# motoko_ice_dragon_x.net
KiCad netlist of a schematic drawn in EasyEDA Pro
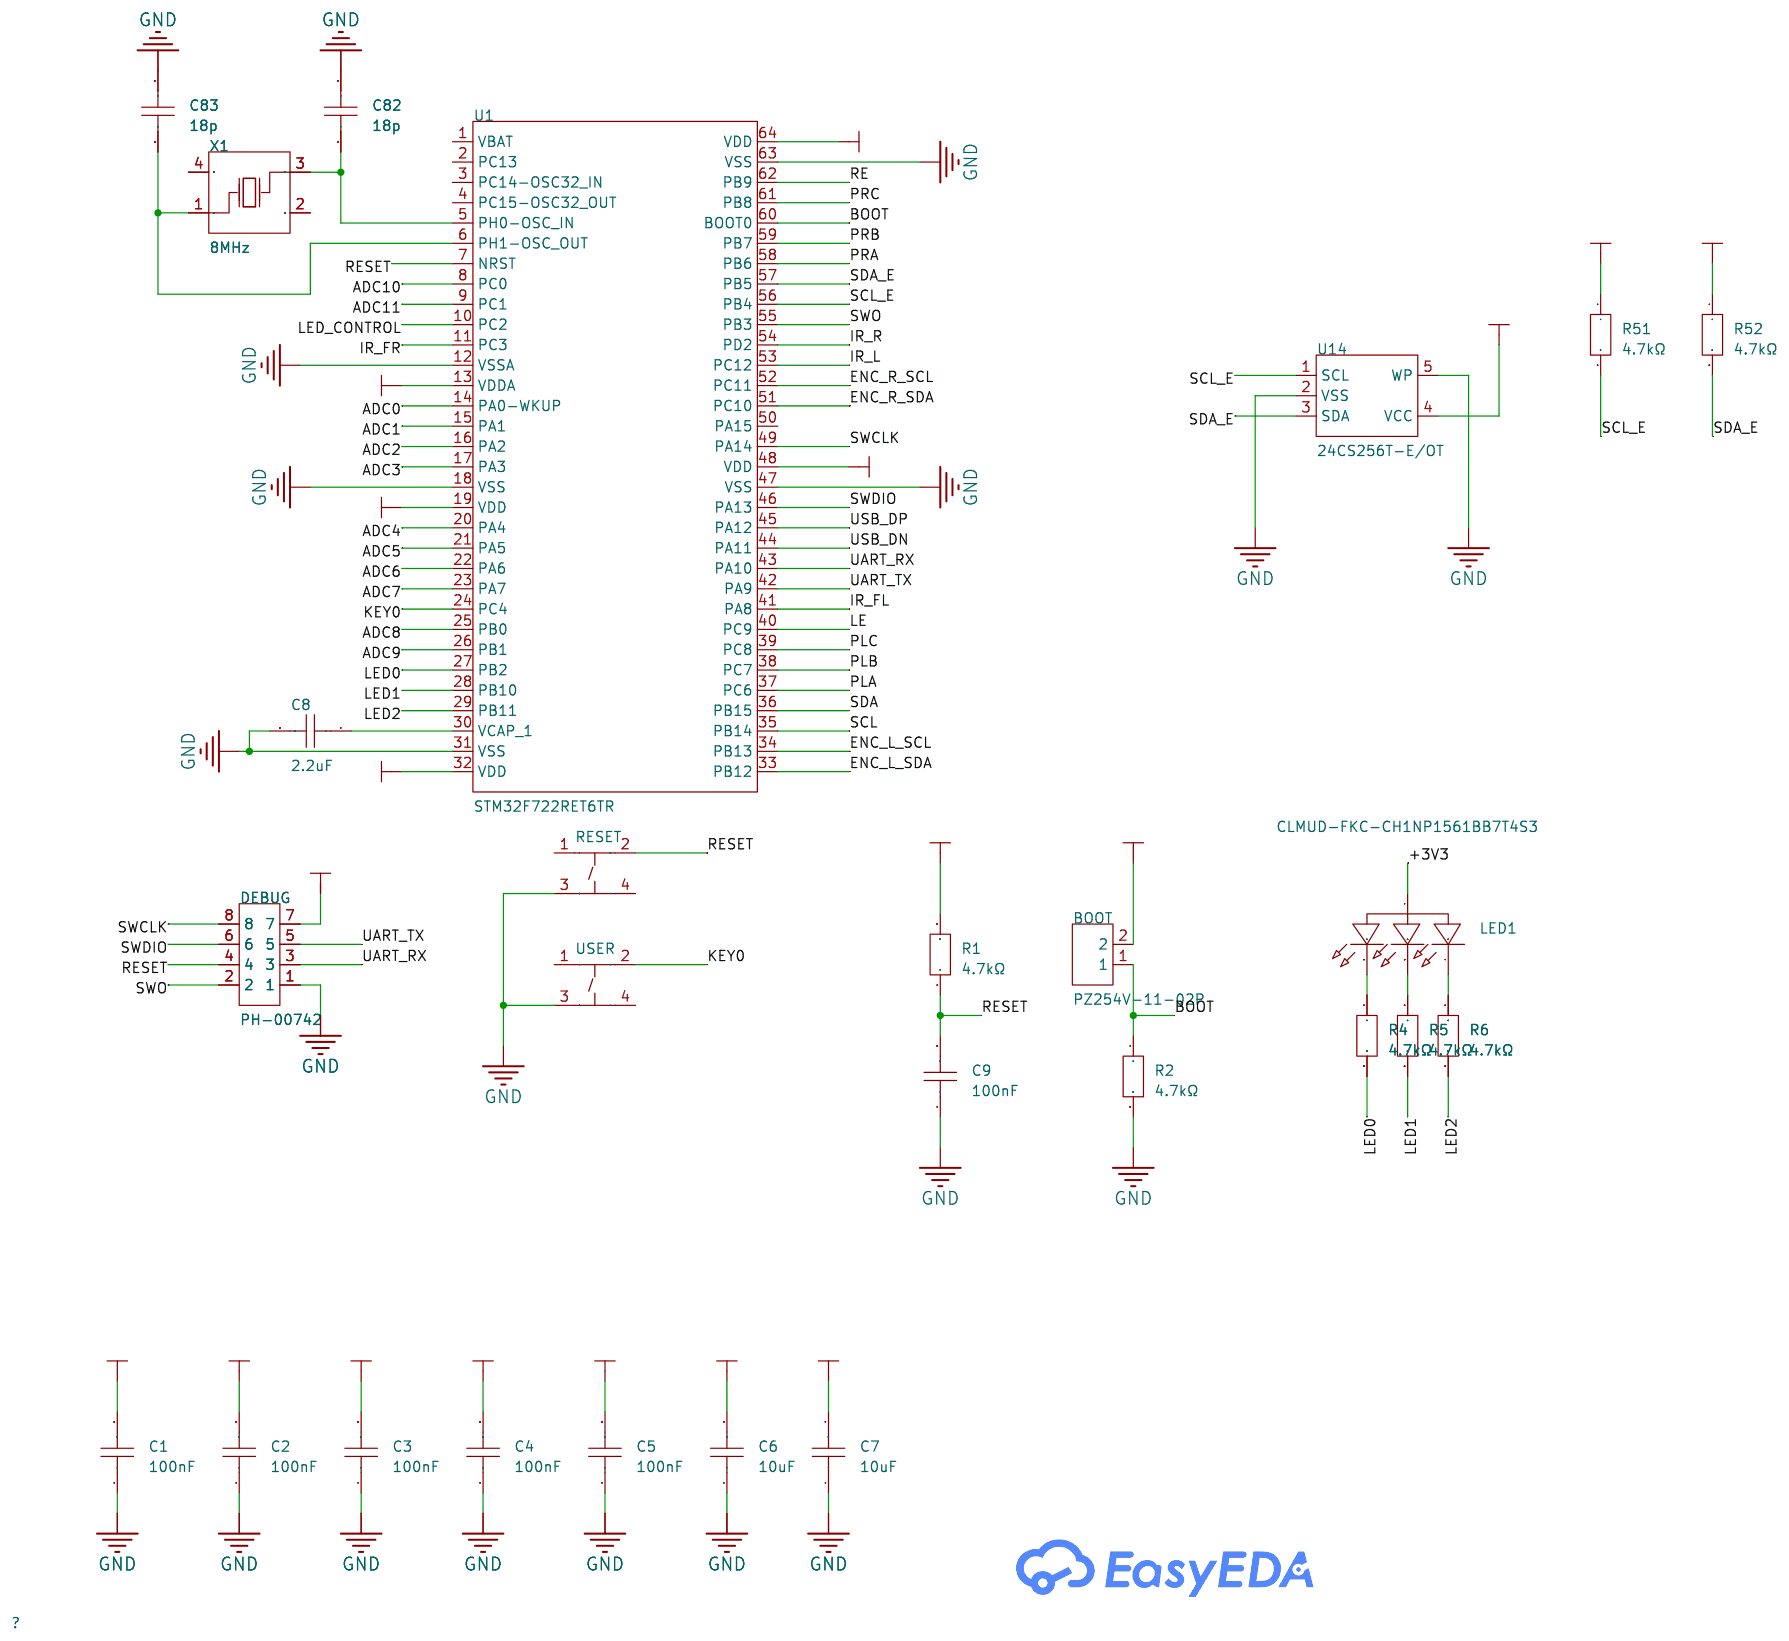
[diagram p0: main]
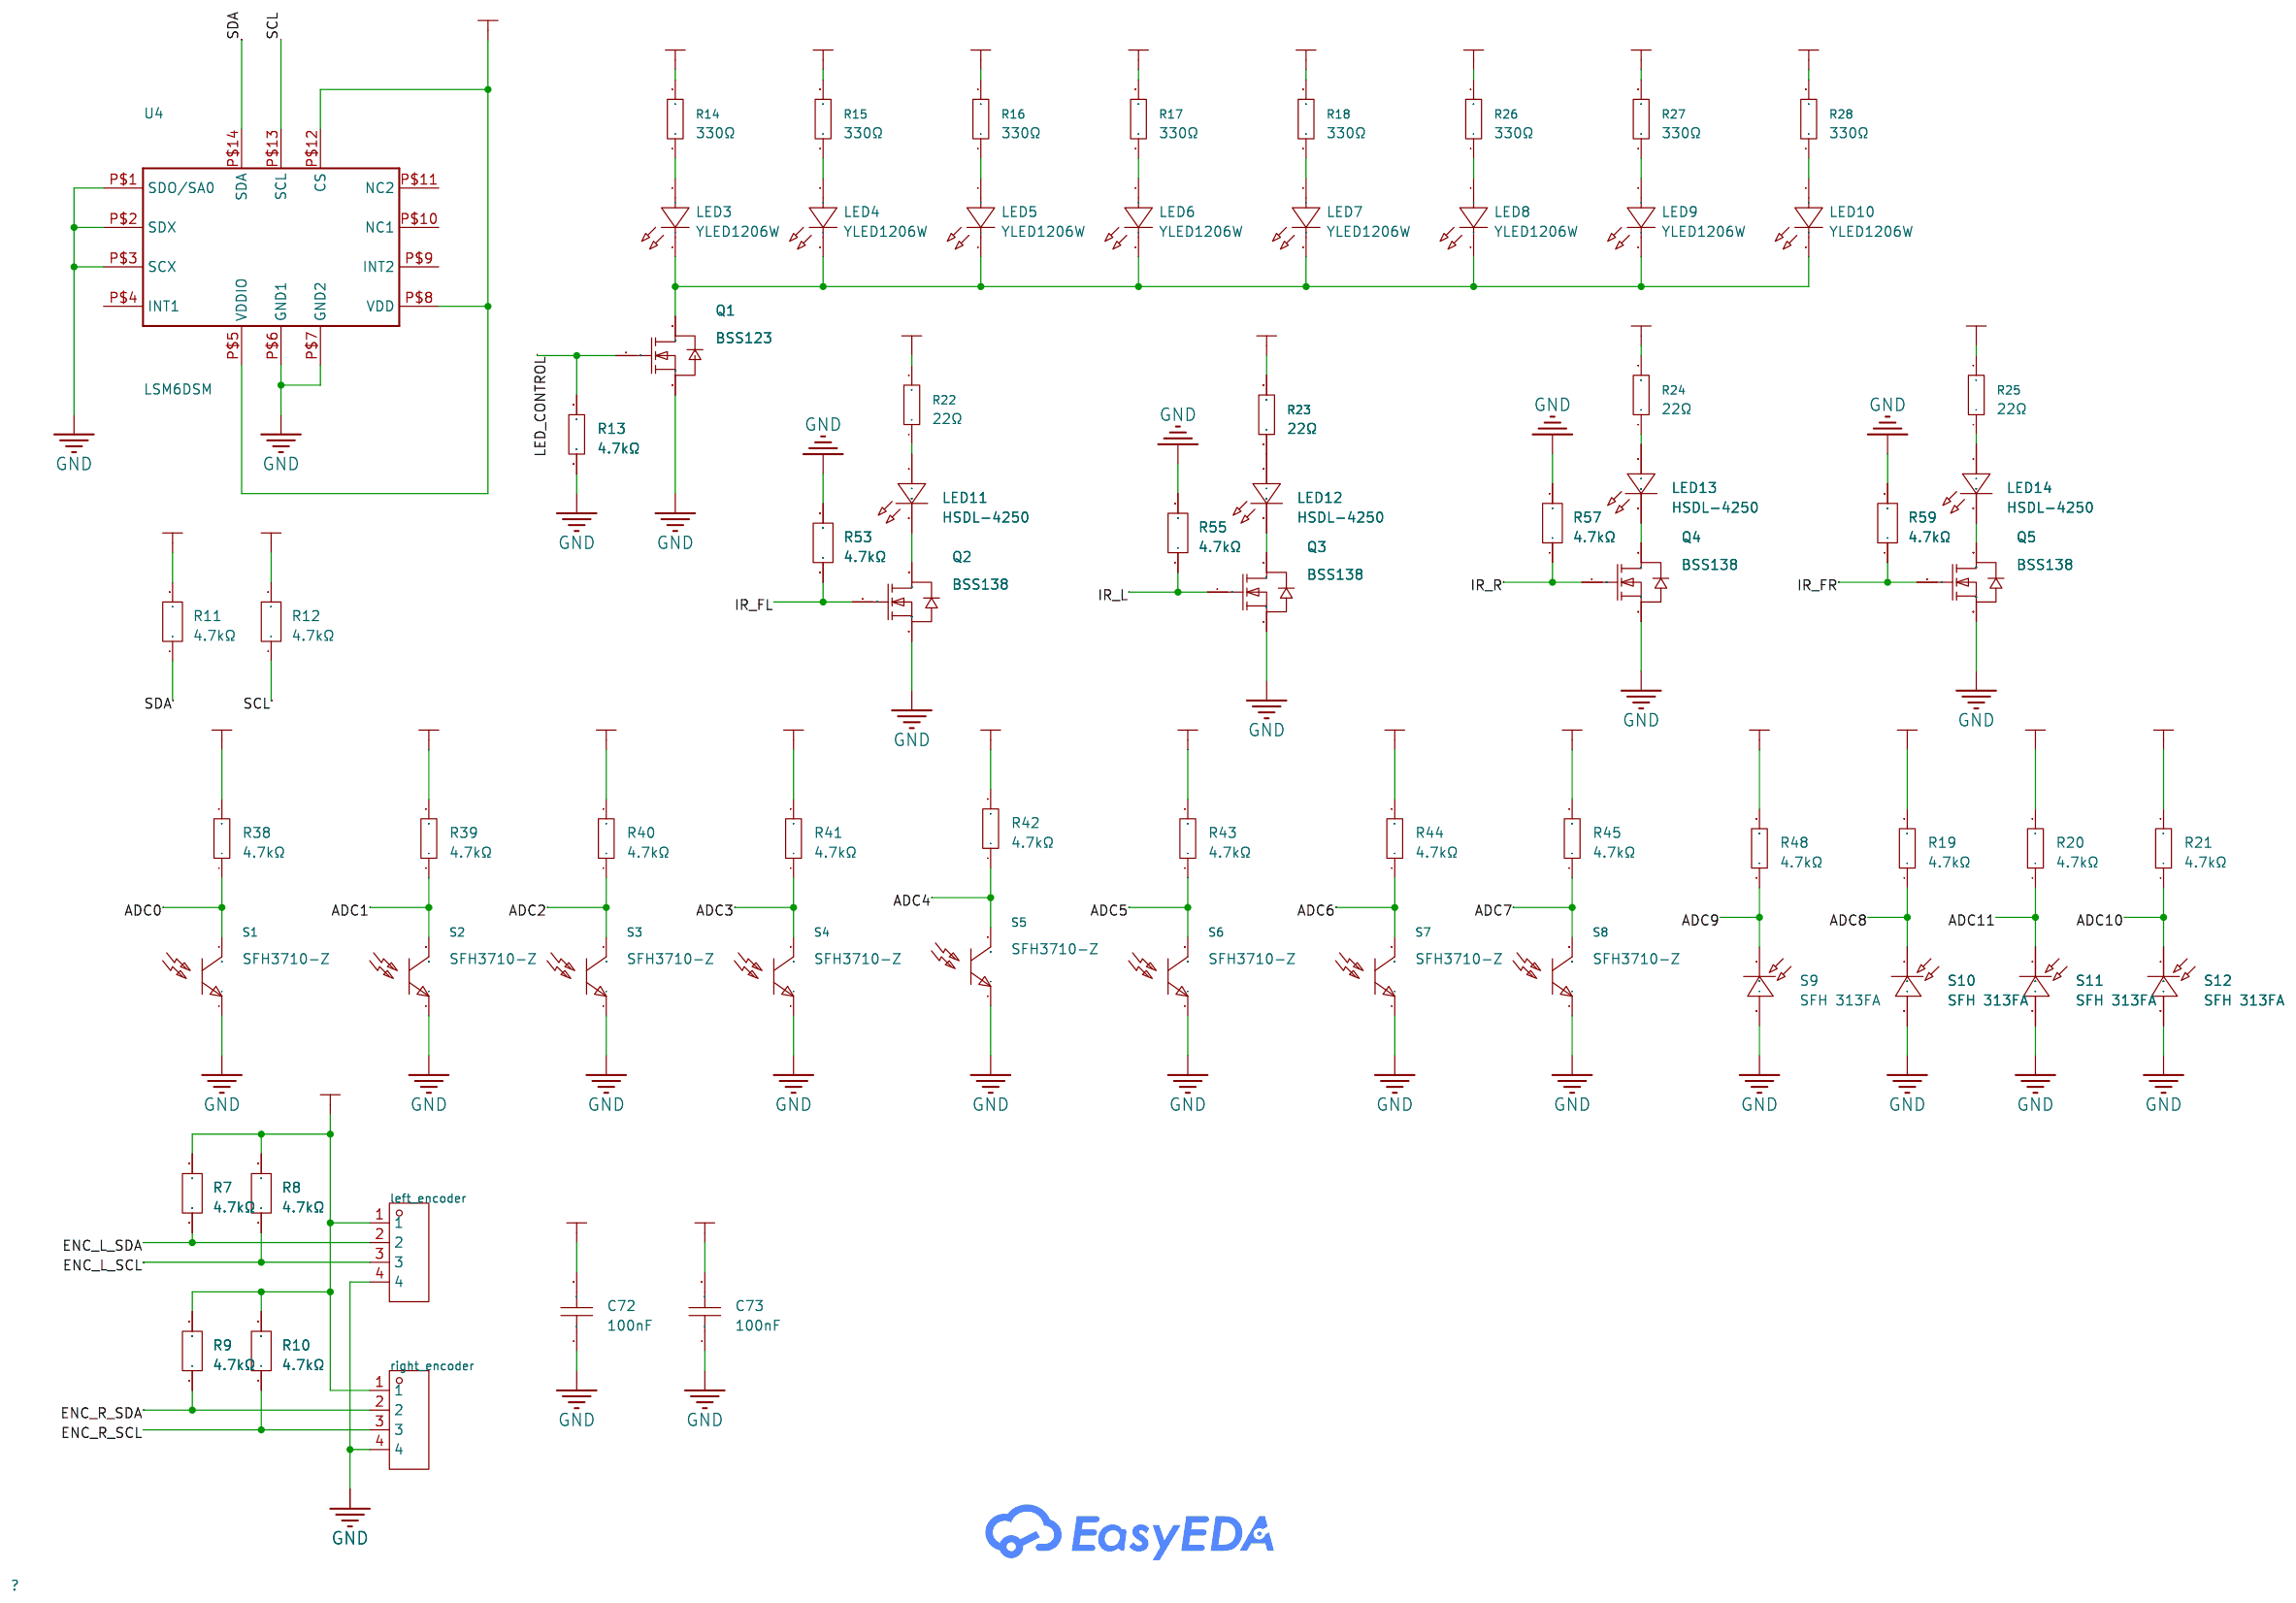
[diagram p1: sensors]
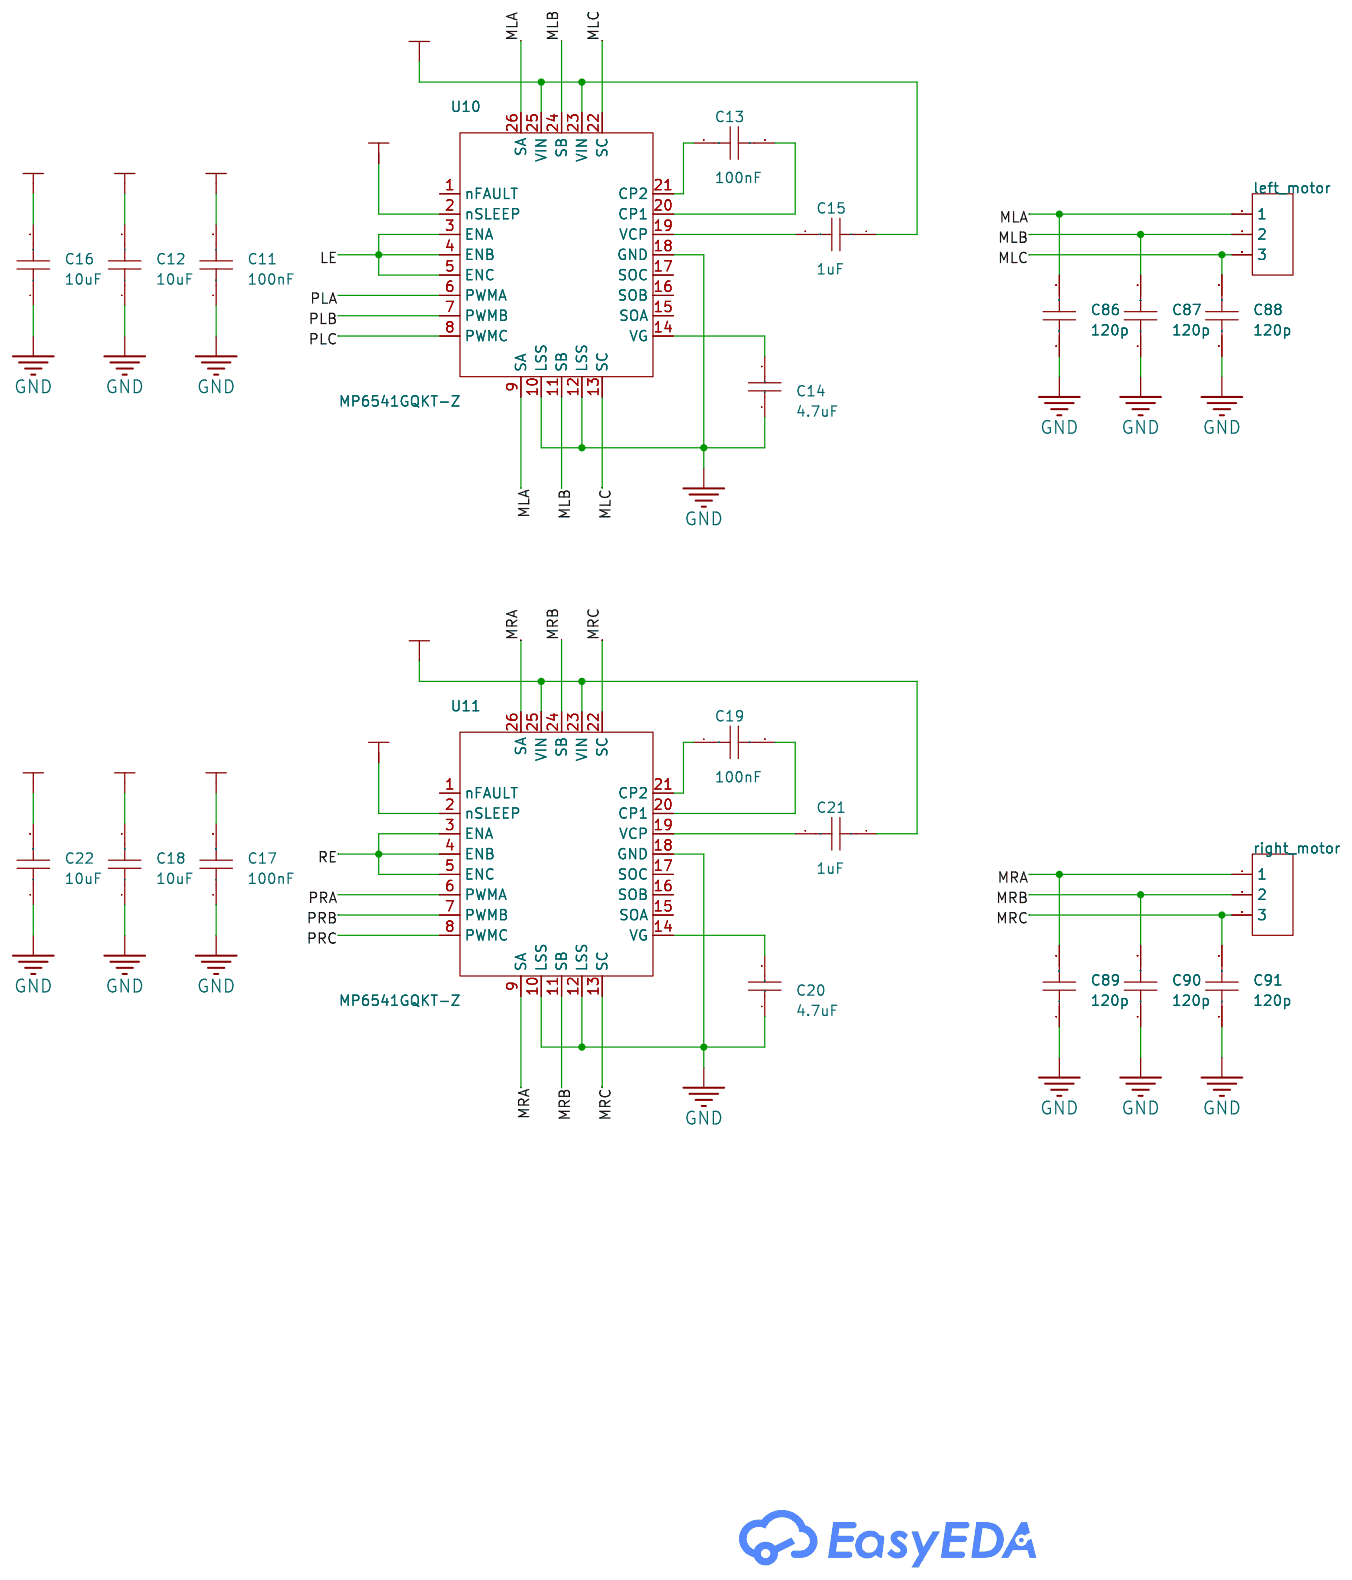
[diagram p2: motors]
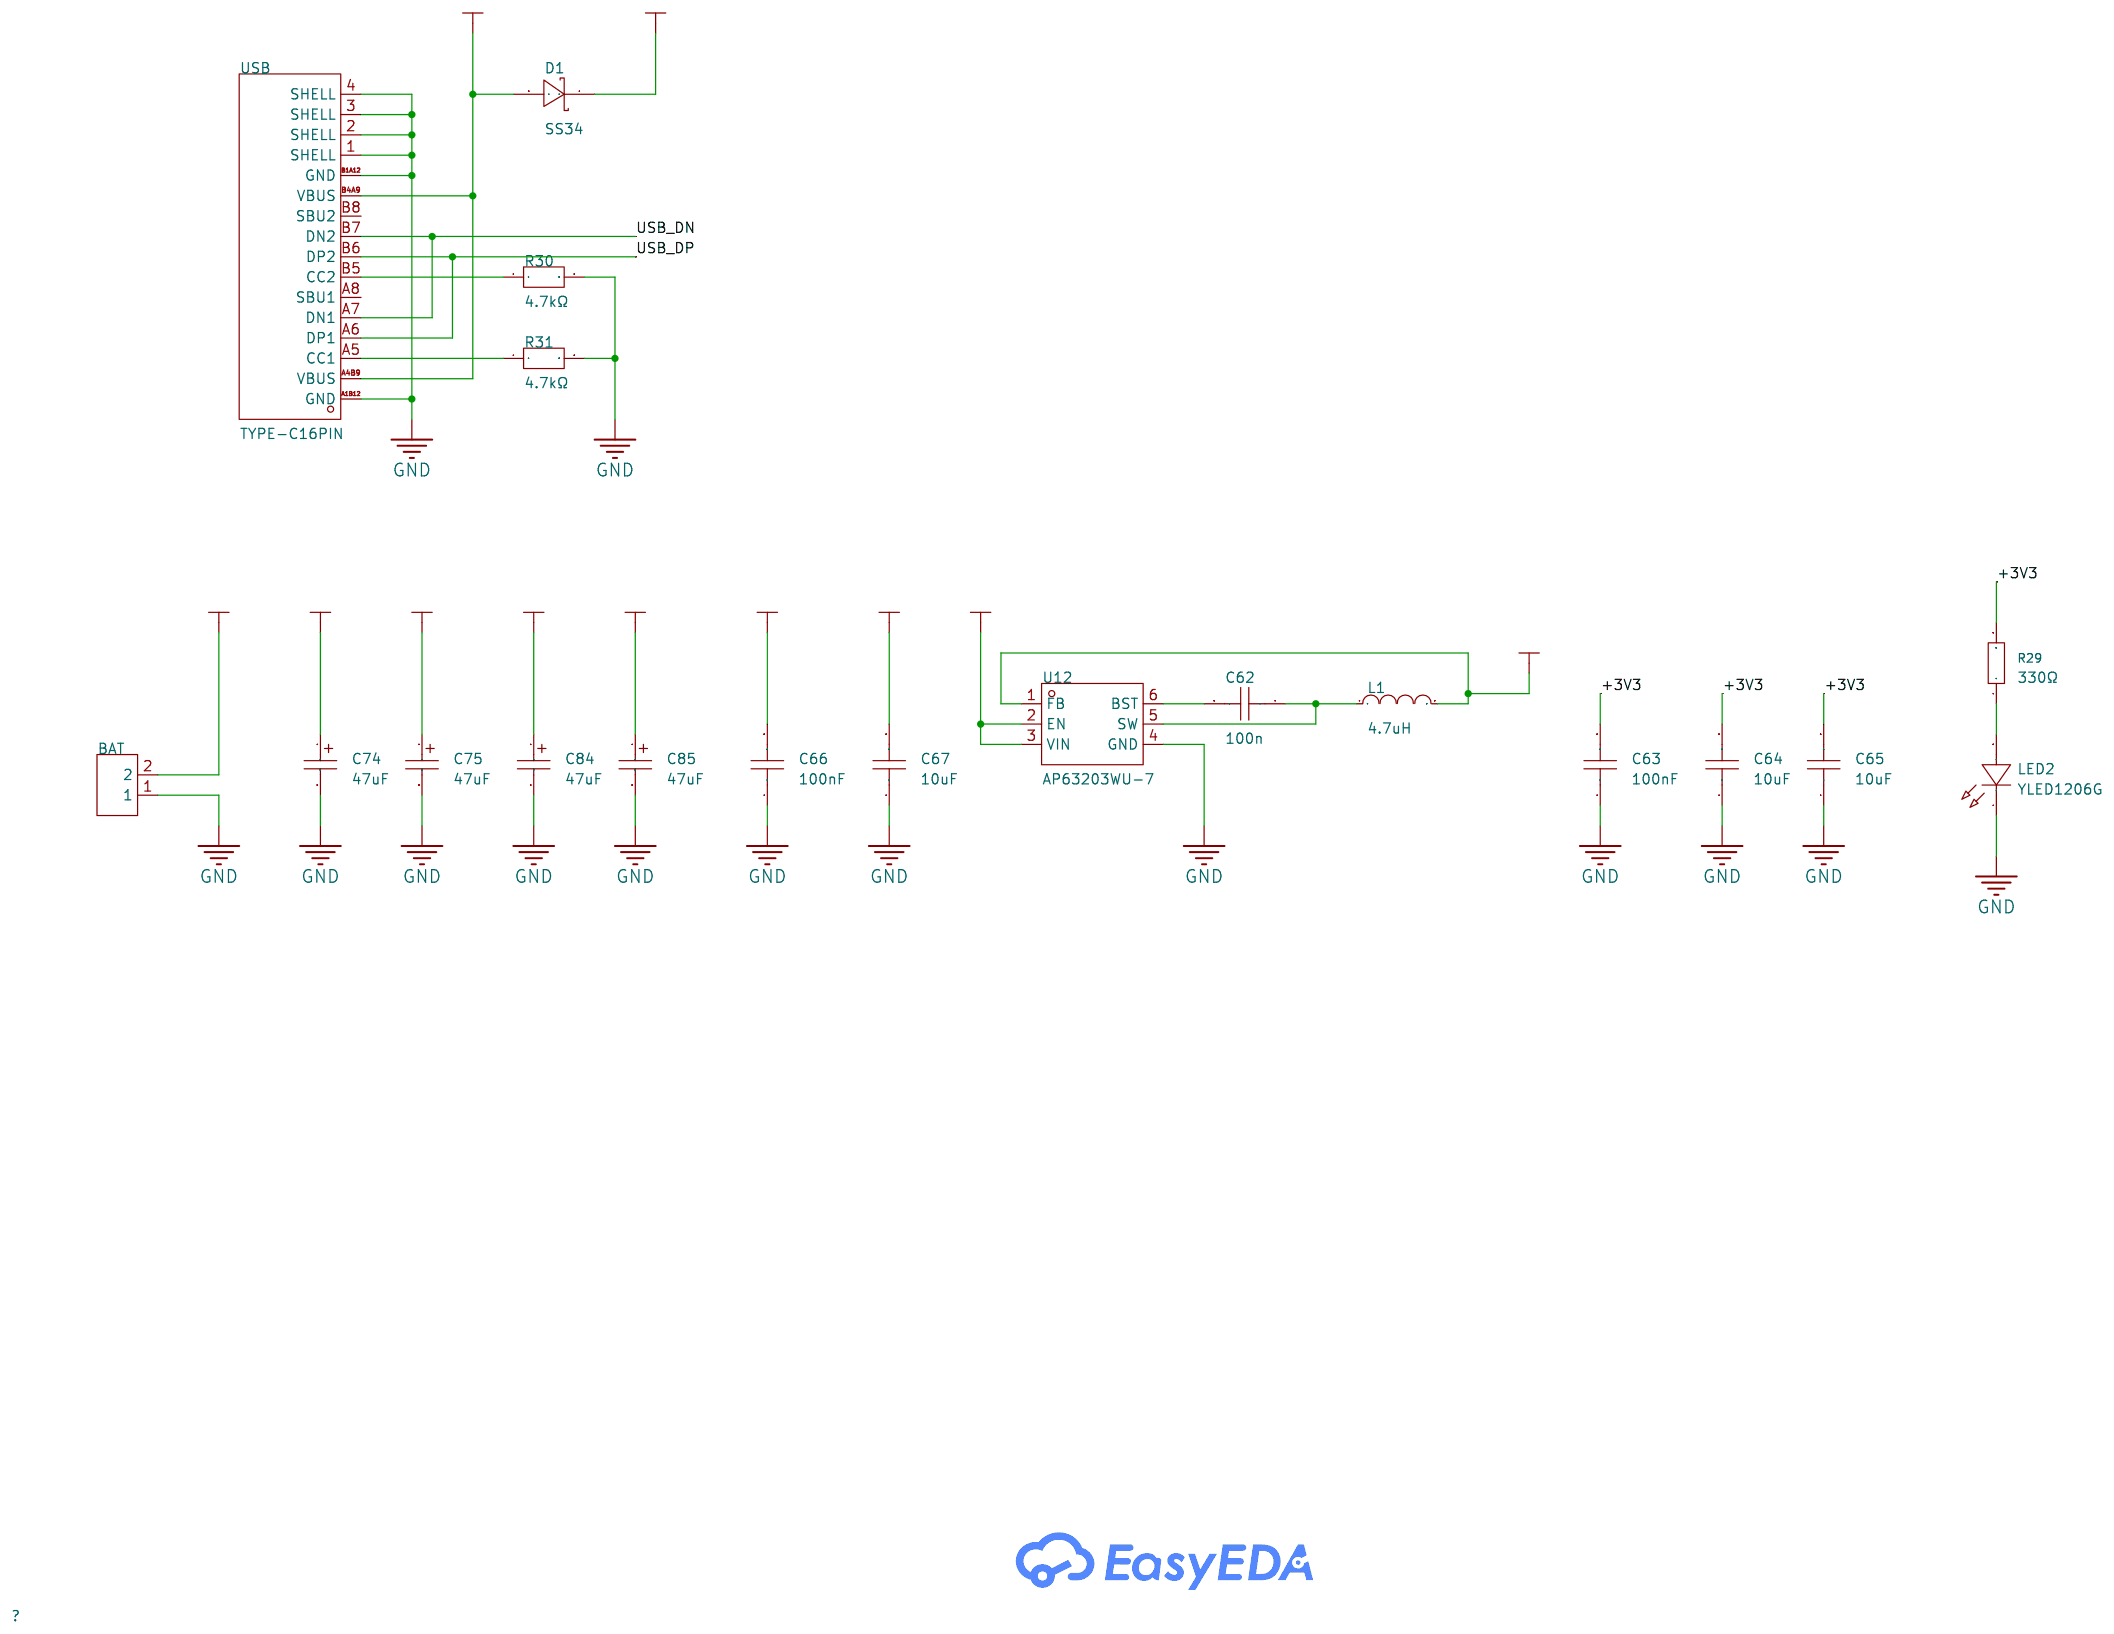
[diagram p3: power]

(export (version "E")
  (design (tool "Eeschema 10.0.6"))
  (components
    (comp (ref "BOOT")
      (value "PZ254V-11-02P")
      (footprint "easyedapro:HDR-TH_2P-P2.54-V-M")
      (fields (field (name "Manufacturer") "XFCN(兴飞)"))
      (libsource (lib "easyedapro") (part "PZ254V-11-02P"))
    )
    (comp (ref "C1")
      (value "100nF")
      (footprint "easyedapro:C0805")
      (description "Capacitance:100nF Tolerance:±10% Tolerance:±10% Voltage Rating:50V Temperature Coefficient:X7R")
      (fields
        (field (name "Manufacturer Part") "CC0805KRX7R9BB104")
        (field (name "Manufacturer") "YAGEO(国巨)")
      )
      (libsource (lib "easyedapro") (part "CC0805KRX7R9BB104"))
    )
    (comp (ref "C2")
      (value "100nF")
      (footprint "easyedapro:C0805")
      (description "Capacitance:100nF Tolerance:±10% Tolerance:±10% Voltage Rating:50V Temperature Coefficient:X7R")
      (fields
        (field (name "Manufacturer Part") "CC0805KRX7R9BB104")
        (field (name "Manufacturer") "YAGEO(国巨)")
      )
      (libsource (lib "easyedapro") (part "CC0805KRX7R9BB104"))
    )
    (comp (ref "C3")
      (value "100nF")
      (footprint "easyedapro:C0805")
      (description "Capacitance:100nF Tolerance:±10% Tolerance:±10% Voltage Rating:50V Temperature Coefficient:X7R")
      (fields
        (field (name "Manufacturer Part") "CC0805KRX7R9BB104")
        (field (name "Manufacturer") "YAGEO(国巨)")
      )
      (libsource (lib "easyedapro") (part "CC0805KRX7R9BB104"))
    )
    (comp (ref "C4")
      (value "100nF")
      (footprint "easyedapro:C0805")
      (description "Capacitance:100nF Tolerance:±10% Tolerance:±10% Voltage Rating:50V Temperature Coefficient:X7R")
      (fields
        (field (name "Manufacturer Part") "CC0805KRX7R9BB104")
        (field (name "Manufacturer") "YAGEO(国巨)")
      )
      (libsource (lib "easyedapro") (part "CC0805KRX7R9BB104"))
    )
    (comp (ref "C5")
      (value "100nF")
      (footprint "easyedapro:C0805")
      (description "Capacitance:100nF Tolerance:±10% Tolerance:±10% Voltage Rating:50V Temperature Coefficient:X7R")
      (fields
        (field (name "Manufacturer Part") "CC0805KRX7R9BB104")
        (field (name "Manufacturer") "YAGEO(国巨)")
      )
      (libsource (lib "easyedapro") (part "CC0805KRX7R9BB104"))
    )
    (comp (ref "C6")
      (value "10uF")
      (footprint "easyedapro:C0805")
      (description "Capacitance:10uF Tolerance:±10% Tolerance:±10% Voltage Rating:50V Temperature Coefficient:X5R")
      (fields
        (field (name "Manufacturer Part") "GRM21BR61H106KE43L")
        (field (name "Manufacturer") "muRata(村田)")
      )
      (libsource (lib "easyedapro") (part "GRM21BR61H106KE43L"))
    )
    (comp (ref "C7")
      (value "10uF")
      (footprint "easyedapro:C0805")
      (description "Capacitance:10uF Tolerance:±10% Tolerance:±10% Voltage Rating:50V Temperature Coefficient:X5R")
      (fields
        (field (name "Manufacturer Part") "GRM21BR61H106KE43L")
        (field (name "Manufacturer") "muRata(村田)")
      )
      (libsource (lib "easyedapro") (part "GRM21BR61H106KE43L"))
    )
    (comp (ref "C8")
      (value "2.2uF")
      (footprint "easyedapro:C0805")
      (description "Capacitance:2.2uF Tolerance:±10% Tolerance:±10% Voltage Rating:50V Temperature Coefficient:X5R")
      (fields
        (field (name "Manufacturer Part") "CL21A225KBQNNNE")
        (field (name "Manufacturer") "SAMSUNG(三星)")
      )
      (libsource (lib "easyedapro") (part "CL21A225KBQNNNE"))
    )
    (comp (ref "C9")
      (value "100nF")
      (footprint "easyedapro:C0805")
      (description "Capacitance:100nF Tolerance:±10% Tolerance:±10% Voltage Rating:50V Temperature Coefficient:X7R")
      (fields
        (field (name "Manufacturer Part") "CC0805KRX7R9BB104")
        (field (name "Manufacturer") "YAGEO(国巨)")
      )
      (libsource (lib "easyedapro") (part "CC0805KRX7R9BB104"))
    )
    (comp (ref "C82")
      (value "18p")
      (footprint "easyedapro:C0805")
      (description "Capacitance:2.2uF Tolerance:±10% Tolerance:±10% Voltage Rating:50V Temperature Coefficient:X5R")
      (fields
        (field (name "Manufacturer Part") "CL21A225KBQNNNE")
        (field (name "Manufacturer") "SAMSUNG(三星)")
      )
      (libsource (lib "easyedapro") (part "CL21A225KBQNNNE"))
    )
    (comp (ref "C83")
      (value "18p")
      (footprint "easyedapro:C0805")
      (description "Capacitance:2.2uF Tolerance:±10% Tolerance:±10% Voltage Rating:50V Temperature Coefficient:X5R")
      (fields
        (field (name "Manufacturer Part") "CL21A225KBQNNNE")
        (field (name "Manufacturer") "SAMSUNG(三星)")
      )
      (libsource (lib "easyedapro") (part "CL21A225KBQNNNE"))
    )
    (comp (ref "DEBUG")
      (value "PH-00742")
      (footprint "easyedapro:HDR-TH_8P-P1.27-V-M-R2-C4-S1.27")
      (fields (field (name "Manufacturer") "Liansheng(连盛)"))
      (libsource (lib "easyedapro") (part "PH-00742"))
    )
    (comp (ref "LED1")
      (value "CLMUD-FKC-CH1NP1561BB7T4S3")
      (footprint "easyedapro:LED-SMD_4P-L1.5-W1.5_CLMUD-FKC-CH1NP1561BB7T4S3")
      (description "Diode Configuration:Common Anode")
      (fields (field (name "Manufacturer") "CREE LED"))
      (libsource (lib "easyedapro") (part "CLMUD-FKC-CH1NP1561BB7T4S3"))
    )
    (comp (ref "R1")
      (value "4.7kΩ")
      (footprint "easyedapro:R0805")
      (fields (field (name "Manufacturer Part") "FRC0805J472 TS") (field (name "Manufacturer") "FOJAN(富捷)"))
      (libsource (lib "easyedapro") (part "FRC0805J472 TS"))
    )
    (comp (ref "R2")
      (value "4.7kΩ")
      (footprint "easyedapro:R0805")
      (fields (field (name "Manufacturer Part") "FRC0805J472 TS") (field (name "Manufacturer") "FOJAN(富捷)"))
      (libsource (lib "easyedapro") (part "FRC0805J472 TS"))
    )
    (comp (ref "R4")
      (value "4.7kΩ")
      (footprint "easyedapro:R0805")
      (fields (field (name "Manufacturer Part") "FRC0805J472 TS") (field (name "Manufacturer") "FOJAN(富捷)"))
      (libsource (lib "easyedapro") (part "FRC0805J472 TS"))
    )
    (comp (ref "R5")
      (value "4.7kΩ")
      (footprint "easyedapro:R0805")
      (fields (field (name "Manufacturer Part") "FRC0805J472 TS") (field (name "Manufacturer") "FOJAN(富捷)"))
      (libsource (lib "easyedapro") (part "FRC0805J472 TS"))
    )
    (comp (ref "R6")
      (value "4.7kΩ")
      (footprint "easyedapro:R0805")
      (fields (field (name "Manufacturer Part") "FRC0805J472 TS") (field (name "Manufacturer") "FOJAN(富捷)"))
      (libsource (lib "easyedapro") (part "FRC0805J472 TS"))
    )
    (comp (ref "R51")
      (value "4.7kΩ")
      (footprint "easyedapro:R0805")
      (fields (field (name "Manufacturer Part") "FRC0805J472 TS") (field (name "Manufacturer") "FOJAN(富捷)"))
      (libsource (lib "easyedapro") (part "FRC0805J472 TS"))
    )
    (comp (ref "R52")
      (value "4.7kΩ")
      (footprint "easyedapro:R0805")
      (fields (field (name "Manufacturer Part") "FRC0805J472 TS") (field (name "Manufacturer") "FOJAN(富捷)"))
      (libsource (lib "easyedapro") (part "FRC0805J472 TS"))
    )
    (comp (ref "RESET")
      (value "TS1705-TZ60HBS")
      (footprint "easyedapro:SW-SMD_4P-L6.2-W6.2-P4.50-LS9.2-2")
      (fields (field (name "Manufacturer") "BXCONN(宝讯)"))
      (libsource (lib "easyedapro") (part "TS1705-TZ60HBS"))
    )
    (comp (ref "U1")
      (value "STM32F722RET6TR")
      (footprint "easyedapro:LQFP-64_L10.0-W10.0-P0.50-LS12.0-BL")
      (fields (field (name "Manufacturer") "ST(意法半导体)"))
      (libsource (lib "easyedapro") (part "STM32F722RET6TR"))
    )
    (comp (ref "U14")
      (value "24CS256T-E/OT")
      (footprint "easyedapro:SOT-23-5_L2.9-W1.6-P0.95-LS2.8-BR")
      (fields (field (name "Manufacturer") "MICROCHIP(美国微芯)"))
      (libsource (lib "easyedapro") (part "24CS256T-E/OT"))
    )
    (comp (ref "USER")
      (value "TS1705-TZ60HBS")
      (footprint "easyedapro:SW-SMD_4P-L6.2-W6.2-P4.50-LS9.2-2")
      (fields (field (name "Manufacturer") "BXCONN(宝讯)"))
      (libsource (lib "easyedapro") (part "TS1705-TZ60HBS"))
    )
    (comp (ref "X1")
      (value "8MHz")
      (footprint "easyedapro:CRYSTAL-SMD_4P-L3.2-W2.5-BL")
      (fields (field (name "Manufacturer Part") "X322512MSB4SI") (field (name "Manufacturer") "YXC(扬兴晶振)"))
      (libsource (lib "easyedapro") (part "X322512MSB4SI"))
    )
    (comp (ref "C72")
      (value "100nF")
      (footprint "easyedapro:C0805")
      (description "Capacitance:100nF Tolerance:±10% Tolerance:±10% Voltage Rating:50V Temperature Coefficient:X7R")
      (fields
        (field (name "Manufacturer Part") "CC0805KRX7R9BB104")
        (field (name "Manufacturer") "YAGEO(国巨)")
      )
      (libsource (lib "easyedapro") (part "CC0805KRX7R9BB104"))
    )
    (comp (ref "C73")
      (value "100nF")
      (footprint "easyedapro:C0805")
      (description "Capacitance:100nF Tolerance:±10% Tolerance:±10% Voltage Rating:50V Temperature Coefficient:X7R")
      (fields
        (field (name "Manufacturer Part") "CC0805KRX7R9BB104")
        (field (name "Manufacturer") "YAGEO(国巨)")
      )
      (libsource (lib "easyedapro") (part "CC0805KRX7R9BB104"))
    )
    (comp (ref "LED3")
      (value "YLED1206W")
      (footprint "easyedapro:LED1206-R-RD")
      (fields (field (name "Manufacturer") "YONGYUTAI(永裕泰)"))
      (libsource (lib "easyedapro") (part "YLED1206W"))
    )
    (comp (ref "LED4")
      (value "YLED1206W")
      (footprint "easyedapro:LED1206-R-RD")
      (fields (field (name "Manufacturer") "YONGYUTAI(永裕泰)"))
      (libsource (lib "easyedapro") (part "YLED1206W"))
    )
    (comp (ref "LED5")
      (value "YLED1206W")
      (footprint "easyedapro:LED1206-R-RD")
      (fields (field (name "Manufacturer") "YONGYUTAI(永裕泰)"))
      (libsource (lib "easyedapro") (part "YLED1206W"))
    )
    (comp (ref "LED6")
      (value "YLED1206W")
      (footprint "easyedapro:LED1206-R-RD")
      (fields (field (name "Manufacturer") "YONGYUTAI(永裕泰)"))
      (libsource (lib "easyedapro") (part "YLED1206W"))
    )
    (comp (ref "LED7")
      (value "YLED1206W")
      (footprint "easyedapro:LED1206-R-RD")
      (fields (field (name "Manufacturer") "YONGYUTAI(永裕泰)"))
      (libsource (lib "easyedapro") (part "YLED1206W"))
    )
    (comp (ref "LED8")
      (value "YLED1206W")
      (footprint "easyedapro:LED1206-R-RD")
      (fields (field (name "Manufacturer") "YONGYUTAI(永裕泰)"))
      (libsource (lib "easyedapro") (part "YLED1206W"))
    )
    (comp (ref "LED9")
      (value "YLED1206W")
      (footprint "easyedapro:LED1206-R-RD")
      (fields (field (name "Manufacturer") "YONGYUTAI(永裕泰)"))
      (libsource (lib "easyedapro") (part "YLED1206W"))
    )
    (comp (ref "LED10")
      (value "YLED1206W")
      (footprint "easyedapro:LED1206-R-RD")
      (fields (field (name "Manufacturer") "YONGYUTAI(永裕泰)"))
      (libsource (lib "easyedapro") (part "YLED1206W"))
    )
    (comp (ref "LED11")
      (value "HSDL-4250")
      (footprint "easyedapro:LED-TH_BD5.0-P2.54-FD-1")
      (fields (field (name "Manufacturer") "LITEON(光宝)"))
      (libsource (lib "easyedapro") (part "HSDL-4250"))
    )
    (comp (ref "LED12")
      (value "HSDL-4250")
      (footprint "easyedapro:LED-TH_BD5.0-P2.54-FD-1")
      (fields (field (name "Manufacturer") "LITEON(光宝)"))
      (libsource (lib "easyedapro") (part "HSDL-4250"))
    )
    (comp (ref "LED13")
      (value "HSDL-4250")
      (footprint "easyedapro:LED-TH_BD5.0-P2.54-FD-1")
      (fields (field (name "Manufacturer") "LITEON(光宝)"))
      (libsource (lib "easyedapro") (part "HSDL-4250"))
    )
    (comp (ref "LED14")
      (value "HSDL-4250")
      (footprint "easyedapro:LED-TH_BD5.0-P2.54-FD-1")
      (fields (field (name "Manufacturer") "LITEON(光宝)"))
      (libsource (lib "easyedapro") (part "HSDL-4250"))
    )
    (comp (ref "left_encoder")
      (value "PZ254V-11-04P")
      (footprint "easyedapro:HDR-TH_4P-P2.54-V-M")
      (fields (field (name "Manufacturer") "XFCN(兴飞)"))
      (libsource (lib "easyedapro") (part "PZ254V-11-04P_C2691448"))
    )
    (comp (ref "Q1")
      (value "BSS123")
      (footprint "easyedapro:SOT-23-3_L3.0-W1.7-P0.95-LS2.9-BR")
      (fields (field (name "Manufacturer") "Siliup(矽普)"))
      (libsource (lib "easyedapro") (part "BSS123_C41355122"))
    )
    (comp (ref "Q2")
      (value "BSS138")
      (footprint "easyedapro:SOT-23-3_L2.9-W1.3-P1.90-LS2.4-BR_1")
      (fields (field (name "Manufacturer") "baocheng(宝乘)"))
      (libsource (lib "easyedapro") (part "BSS138_C51898309"))
    )
    (comp (ref "Q3")
      (value "BSS138")
      (footprint "easyedapro:SOT-23-3_L2.9-W1.3-P1.90-LS2.4-BR_1")
      (fields (field (name "Manufacturer") "baocheng(宝乘)"))
      (libsource (lib "easyedapro") (part "BSS138_C51898309"))
    )
    (comp (ref "Q4")
      (value "BSS138")
      (footprint "easyedapro:SOT-23-3_L2.9-W1.3-P1.90-LS2.4-BR_1")
      (fields (field (name "Manufacturer") "baocheng(宝乘)"))
      (libsource (lib "easyedapro") (part "BSS138_C51898309"))
    )
    (comp (ref "Q5")
      (value "BSS138")
      (footprint "easyedapro:SOT-23-3_L2.9-W1.3-P1.90-LS2.4-BR_1")
      (fields (field (name "Manufacturer") "baocheng(宝乘)"))
      (libsource (lib "easyedapro") (part "BSS138_C51898309"))
    )
    (comp (ref "R7")
      (value "4.7kΩ")
      (footprint "easyedapro:R0805")
      (fields (field (name "Manufacturer Part") "FRC0805J472 TS") (field (name "Manufacturer") "FOJAN(富捷)"))
      (libsource (lib "easyedapro") (part "FRC0805J472 TS"))
    )
    (comp (ref "R8")
      (value "4.7kΩ")
      (footprint "easyedapro:R0805")
      (fields (field (name "Manufacturer Part") "FRC0805J472 TS") (field (name "Manufacturer") "FOJAN(富捷)"))
      (libsource (lib "easyedapro") (part "FRC0805J472 TS"))
    )
    (comp (ref "R9")
      (value "4.7kΩ")
      (footprint "easyedapro:R0805")
      (fields (field (name "Manufacturer Part") "FRC0805J472 TS") (field (name "Manufacturer") "FOJAN(富捷)"))
      (libsource (lib "easyedapro") (part "FRC0805J472 TS"))
    )
    (comp (ref "R10")
      (value "4.7kΩ")
      (footprint "easyedapro:R0805")
      (fields (field (name "Manufacturer Part") "FRC0805J472 TS") (field (name "Manufacturer") "FOJAN(富捷)"))
      (libsource (lib "easyedapro") (part "FRC0805J472 TS"))
    )
    (comp (ref "R11")
      (value "4.7kΩ")
      (footprint "easyedapro:R0805")
      (fields (field (name "Manufacturer Part") "FRC0805J472 TS") (field (name "Manufacturer") "FOJAN(富捷)"))
      (libsource (lib "easyedapro") (part "FRC0805J472 TS"))
    )
    (comp (ref "R12")
      (value "4.7kΩ")
      (footprint "easyedapro:R0805")
      (fields (field (name "Manufacturer Part") "FRC0805J472 TS") (field (name "Manufacturer") "FOJAN(富捷)"))
      (libsource (lib "easyedapro") (part "FRC0805J472 TS"))
    )
    (comp (ref "R13")
      (value "4.7kΩ")
      (footprint "easyedapro:R0805")
      (fields
        (field (name "Manufacturer Part") "0805W8F4701T5E")
        (field (name "Manufacturer") "UNI-ROYAL(厚声)")
      )
      (libsource (lib "easyedapro") (part "0805W8F4701T5E"))
    )
    (comp (ref "R14")
      (value "330Ω")
      (footprint "easyedapro:R0805")
      (fields
        (field (name "Manufacturer Part") "0805W8F3300T5E")
        (field (name "Manufacturer") "UNI-ROYAL(厚声)")
      )
      (libsource (lib "easyedapro") (part "0805W8F3300T5E"))
    )
    (comp (ref "R15")
      (value "330Ω")
      (footprint "easyedapro:R0805")
      (fields
        (field (name "Manufacturer Part") "0805W8F3300T5E")
        (field (name "Manufacturer") "UNI-ROYAL(厚声)")
      )
      (libsource (lib "easyedapro") (part "0805W8F3300T5E"))
    )
    (comp (ref "R16")
      (value "330Ω")
      (footprint "easyedapro:R0805")
      (fields
        (field (name "Manufacturer Part") "0805W8F3300T5E")
        (field (name "Manufacturer") "UNI-ROYAL(厚声)")
      )
      (libsource (lib "easyedapro") (part "0805W8F3300T5E"))
    )
    (comp (ref "R17")
      (value "330Ω")
      (footprint "easyedapro:R0805")
      (fields
        (field (name "Manufacturer Part") "0805W8F3300T5E")
        (field (name "Manufacturer") "UNI-ROYAL(厚声)")
      )
      (libsource (lib "easyedapro") (part "0805W8F3300T5E"))
    )
    (comp (ref "R18")
      (value "330Ω")
      (footprint "easyedapro:R0805")
      (fields
        (field (name "Manufacturer Part") "0805W8F3300T5E")
        (field (name "Manufacturer") "UNI-ROYAL(厚声)")
      )
      (libsource (lib "easyedapro") (part "0805W8F3300T5E"))
    )
    (comp (ref "R19")
      (value "4.7kΩ")
      (footprint "easyedapro:R0805")
      (fields
        (field (name "Manufacturer Part") "0805W8F4701T5E")
        (field (name "Manufacturer") "UNI-ROYAL(厚声)")
      )
      (libsource (lib "easyedapro") (part "0805W8F4701T5E"))
    )
    (comp (ref "R20")
      (value "4.7kΩ")
      (footprint "easyedapro:R0805")
      (fields
        (field (name "Manufacturer Part") "0805W8F4701T5E")
        (field (name "Manufacturer") "UNI-ROYAL(厚声)")
      )
      (libsource (lib "easyedapro") (part "0805W8F4701T5E"))
    )
    (comp (ref "R21")
      (value "4.7kΩ")
      (footprint "easyedapro:R0805")
      (fields
        (field (name "Manufacturer Part") "0805W8F4701T5E")
        (field (name "Manufacturer") "UNI-ROYAL(厚声)")
      )
      (libsource (lib "easyedapro") (part "0805W8F4701T5E"))
    )
    (comp (ref "R22")
      (value "22Ω")
      (footprint "easyedapro:R0805")
      (fields
        (field (name "Manufacturer Part") "0805W8F3300T5E")
        (field (name "Manufacturer") "UNI-ROYAL(厚声)")
      )
      (libsource (lib "easyedapro") (part "0805W8F3300T5E"))
    )
    (comp (ref "R23")
      (value "22Ω")
      (footprint "easyedapro:R0805")
      (fields
        (field (name "Manufacturer Part") "0805W8F3300T5E")
        (field (name "Manufacturer") "UNI-ROYAL(厚声)")
      )
      (libsource (lib "easyedapro") (part "0805W8F3300T5E"))
    )
    (comp (ref "R24")
      (value "22Ω")
      (footprint "easyedapro:R0805")
      (fields
        (field (name "Manufacturer Part") "0805W8F3300T5E")
        (field (name "Manufacturer") "UNI-ROYAL(厚声)")
      )
      (libsource (lib "easyedapro") (part "0805W8F3300T5E"))
    )
    (comp (ref "R25")
      (value "22Ω")
      (footprint "easyedapro:R0805")
      (fields
        (field (name "Manufacturer Part") "0805W8F3300T5E")
        (field (name "Manufacturer") "UNI-ROYAL(厚声)")
      )
      (libsource (lib "easyedapro") (part "0805W8F3300T5E"))
    )
    (comp (ref "R26")
      (value "330Ω")
      (footprint "easyedapro:R0805")
      (fields
        (field (name "Manufacturer Part") "0805W8F3300T5E")
        (field (name "Manufacturer") "UNI-ROYAL(厚声)")
      )
      (libsource (lib "easyedapro") (part "0805W8F3300T5E"))
    )
    (comp (ref "R27")
      (value "330Ω")
      (footprint "easyedapro:R0805")
      (fields
        (field (name "Manufacturer Part") "0805W8F3300T5E")
        (field (name "Manufacturer") "UNI-ROYAL(厚声)")
      )
      (libsource (lib "easyedapro") (part "0805W8F3300T5E"))
    )
    (comp (ref "R28")
      (value "330Ω")
      (footprint "easyedapro:R0805")
      (fields
        (field (name "Manufacturer Part") "0805W8F3300T5E")
        (field (name "Manufacturer") "UNI-ROYAL(厚声)")
      )
      (libsource (lib "easyedapro") (part "0805W8F3300T5E"))
    )
    (comp (ref "R38")
      (value "4.7kΩ")
      (footprint "easyedapro:R0805")
      (fields
        (field (name "Manufacturer Part") "0805W8F4701T5E")
        (field (name "Manufacturer") "UNI-ROYAL(厚声)")
      )
      (libsource (lib "easyedapro") (part "0805W8F4701T5E"))
    )
    (comp (ref "R39")
      (value "4.7kΩ")
      (footprint "easyedapro:R0805")
      (fields
        (field (name "Manufacturer Part") "0805W8F4701T5E")
        (field (name "Manufacturer") "UNI-ROYAL(厚声)")
      )
      (libsource (lib "easyedapro") (part "0805W8F4701T5E"))
    )
    (comp (ref "R40")
      (value "4.7kΩ")
      (footprint "easyedapro:R0805")
      (fields
        (field (name "Manufacturer Part") "0805W8F4701T5E")
        (field (name "Manufacturer") "UNI-ROYAL(厚声)")
      )
      (libsource (lib "easyedapro") (part "0805W8F4701T5E"))
    )
    (comp (ref "R41")
      (value "4.7kΩ")
      (footprint "easyedapro:R0805")
      (fields
        (field (name "Manufacturer Part") "0805W8F4701T5E")
        (field (name "Manufacturer") "UNI-ROYAL(厚声)")
      )
      (libsource (lib "easyedapro") (part "0805W8F4701T5E"))
    )
    (comp (ref "R42")
      (value "4.7kΩ")
      (footprint "easyedapro:R0805")
      (fields
        (field (name "Manufacturer Part") "0805W8F4701T5E")
        (field (name "Manufacturer") "UNI-ROYAL(厚声)")
      )
      (libsource (lib "easyedapro") (part "0805W8F4701T5E"))
    )
    (comp (ref "R43")
      (value "4.7kΩ")
      (footprint "easyedapro:R0805")
      (fields
        (field (name "Manufacturer Part") "0805W8F4701T5E")
        (field (name "Manufacturer") "UNI-ROYAL(厚声)")
      )
      (libsource (lib "easyedapro") (part "0805W8F4701T5E"))
    )
    (comp (ref "R44")
      (value "4.7kΩ")
      (footprint "easyedapro:R0805")
      (fields
        (field (name "Manufacturer Part") "0805W8F4701T5E")
        (field (name "Manufacturer") "UNI-ROYAL(厚声)")
      )
      (libsource (lib "easyedapro") (part "0805W8F4701T5E"))
    )
    (comp (ref "R45")
      (value "4.7kΩ")
      (footprint "easyedapro:R0805")
      (fields
        (field (name "Manufacturer Part") "0805W8F4701T5E")
        (field (name "Manufacturer") "UNI-ROYAL(厚声)")
      )
      (libsource (lib "easyedapro") (part "0805W8F4701T5E"))
    )
    (comp (ref "R48")
      (value "4.7kΩ")
      (footprint "easyedapro:R0805")
      (fields
        (field (name "Manufacturer Part") "0805W8F4701T5E")
        (field (name "Manufacturer") "UNI-ROYAL(厚声)")
      )
      (libsource (lib "easyedapro") (part "0805W8F4701T5E"))
    )
    (comp (ref "R53")
      (value "4.7kΩ")
      (footprint "easyedapro:R0805")
      (fields (field (name "Manufacturer Part") "FRC0805J472 TS") (field (name "Manufacturer") "FOJAN(富捷)"))
      (libsource (lib "easyedapro") (part "FRC0805J472 TS"))
    )
    (comp (ref "R55")
      (value "4.7kΩ")
      (footprint "easyedapro:R0805")
      (fields (field (name "Manufacturer Part") "FRC0805J472 TS") (field (name "Manufacturer") "FOJAN(富捷)"))
      (libsource (lib "easyedapro") (part "FRC0805J472 TS"))
    )
    (comp (ref "R57")
      (value "4.7kΩ")
      (footprint "easyedapro:R0805")
      (fields (field (name "Manufacturer Part") "FRC0805J472 TS") (field (name "Manufacturer") "FOJAN(富捷)"))
      (libsource (lib "easyedapro") (part "FRC0805J472 TS"))
    )
    (comp (ref "R59")
      (value "4.7kΩ")
      (footprint "easyedapro:R0805")
      (fields (field (name "Manufacturer Part") "FRC0805J472 TS") (field (name "Manufacturer") "FOJAN(富捷)"))
      (libsource (lib "easyedapro") (part "FRC0805J472 TS"))
    )
    (comp (ref "right_encoder")
      (value "PZ254V-11-04P")
      (footprint "easyedapro:HDR-TH_4P-P2.54-V-M")
      (fields (field (name "Manufacturer") "XFCN(兴飞)"))
      (libsource (lib "easyedapro") (part "PZ254V-11-04P_C2691448"))
    )
    (comp (ref "S1")
      (value "SFH3710-Z")
      (footprint "easyedapro:OPTO-SMD_SFH3710-Z")
      (fields (field (name "Manufacturer") "OSRAM(欧司朗)"))
      (libsource (lib "easyedapro") (part "SFH3710-Z"))
    )
    (comp (ref "S2")
      (value "SFH3710-Z")
      (footprint "easyedapro:OPTO-SMD_SFH3710-Z")
      (fields (field (name "Manufacturer") "OSRAM(欧司朗)"))
      (libsource (lib "easyedapro") (part "SFH3710-Z"))
    )
    (comp (ref "S3")
      (value "SFH3710-Z")
      (footprint "easyedapro:OPTO-SMD_SFH3710-Z")
      (fields (field (name "Manufacturer") "OSRAM(欧司朗)"))
      (libsource (lib "easyedapro") (part "SFH3710-Z"))
    )
    (comp (ref "S4")
      (value "SFH3710-Z")
      (footprint "easyedapro:OPTO-SMD_SFH3710-Z")
      (fields (field (name "Manufacturer") "OSRAM(欧司朗)"))
      (libsource (lib "easyedapro") (part "SFH3710-Z"))
    )
    (comp (ref "S5")
      (value "SFH3710-Z")
      (footprint "easyedapro:OPTO-SMD_SFH3710-Z")
      (fields (field (name "Manufacturer") "OSRAM(欧司朗)"))
      (libsource (lib "easyedapro") (part "SFH3710-Z"))
    )
    (comp (ref "S6")
      (value "SFH3710-Z")
      (footprint "easyedapro:OPTO-SMD_SFH3710-Z")
      (fields (field (name "Manufacturer") "OSRAM(欧司朗)"))
      (libsource (lib "easyedapro") (part "SFH3710-Z"))
    )
    (comp (ref "S7")
      (value "SFH3710-Z")
      (footprint "easyedapro:OPTO-SMD_SFH3710-Z")
      (fields (field (name "Manufacturer") "OSRAM(欧司朗)"))
      (libsource (lib "easyedapro") (part "SFH3710-Z"))
    )
    (comp (ref "S8")
      (value "SFH3710-Z")
      (footprint "easyedapro:OPTO-SMD_SFH3710-Z")
      (fields (field (name "Manufacturer") "OSRAM(欧司朗)"))
      (libsource (lib "easyedapro") (part "SFH3710-Z"))
    )
    (comp (ref "S9")
      (value "SFH 313FA")
      (footprint "easyedapro:OPTO-TH_BD5.7-P2.54-D0.8")
      (fields (field (name "Manufacturer") "OSRAM(欧司朗)"))
      (libsource (lib "easyedapro") (part "SFH 313FA"))
    )
    (comp (ref "S10")
      (value "SFH 313FA")
      (footprint "easyedapro:OPTO-TH_BD5.7-P2.54-D0.8")
      (fields (field (name "Manufacturer") "OSRAM(欧司朗)"))
      (libsource (lib "easyedapro") (part "SFH 313FA"))
    )
    (comp (ref "S11")
      (value "SFH 313FA")
      (footprint "easyedapro:OPTO-TH_BD5.7-P2.54-D0.8")
      (fields (field (name "Manufacturer") "OSRAM(欧司朗)"))
      (libsource (lib "easyedapro") (part "SFH 313FA"))
    )
    (comp (ref "S12")
      (value "SFH 313FA")
      (footprint "easyedapro:OPTO-TH_BD5.7-P2.54-D0.8")
      (fields (field (name "Manufacturer") "OSRAM(欧司朗)"))
      (libsource (lib "easyedapro") (part "SFH 313FA"))
    )
    (comp (ref "U4")
      (value "LSM6DSM")
      (footprint "easyedapro:LGA14L")
      (libsource (lib "easyedapro") (part "LSM6DSM"))
    )
    (comp (ref "C11")
      (value "100nF")
      (footprint "easyedapro:C0805")
      (description "Capacitance:100nF Tolerance:±10% Tolerance:±10% Voltage Rating:50V Temperature Coefficient:X7R")
      (fields
        (field (name "Manufacturer Part") "CC0805KRX7R9BB104")
        (field (name "Manufacturer") "YAGEO(国巨)")
      )
      (libsource (lib "easyedapro") (part "CC0805KRX7R9BB104"))
    )
    (comp (ref "C12")
      (value "10uF")
      (footprint "easyedapro:C0805")
      (description "Capacitance:10uF Tolerance:±10% Tolerance:±10% Voltage Rating:50V Temperature Coefficient:X5R")
      (fields
        (field (name "Manufacturer Part") "GRM21BR61H106KE43L")
        (field (name "Manufacturer") "muRata(村田)")
      )
      (libsource (lib "easyedapro") (part "GRM21BR61H106KE43L"))
    )
    (comp (ref "C13")
      (value "100nF")
      (footprint "easyedapro:C0805")
      (description "Capacitance:100nF Tolerance:±10% Tolerance:±10% Voltage Rating:50V Temperature Coefficient:X7R")
      (fields
        (field (name "Manufacturer Part") "CC0805KRX7R9BB104")
        (field (name "Manufacturer") "YAGEO(国巨)")
      )
      (libsource (lib "easyedapro") (part "CC0805KRX7R9BB104"))
    )
    (comp (ref "C14")
      (value "4.7uF")
      (footprint "easyedapro:C0805")
      (description "Capacitance:4.7uF Tolerance:±10% Tolerance:±10% Voltage Rating:25V Temperature Coefficient:X5R")
      (fields
        (field (name "Manufacturer Part") "CL21A475KAQNNNE")
        (field (name "Manufacturer") "SAMSUNG(三星)")
      )
      (libsource (lib "easyedapro") (part "CL21A475KAQNNNE"))
    )
    (comp (ref "C15")
      (value "1uF")
      (footprint "easyedapro:C0805")
      (description "Capacitance:1uF Tolerance:±20% Tolerance:±20% Voltage Rating:50V Temperature Coefficient:X7R")
      (fields
        (field (name "Manufacturer Part") "TCC0805X7R105M500FT")
        (field (name "Manufacturer") "CCTC(三环)")
      )
      (libsource (lib "easyedapro") (part "TCC0805X7R105M500FT"))
    )
    (comp (ref "C16")
      (value "10uF")
      (footprint "easyedapro:C0805")
      (description "Capacitance:10uF Tolerance:±10% Tolerance:±10% Voltage Rating:50V Temperature Coefficient:X5R")
      (fields
        (field (name "Manufacturer Part") "GRM21BR61H106KE43L")
        (field (name "Manufacturer") "muRata(村田)")
      )
      (libsource (lib "easyedapro") (part "GRM21BR61H106KE43L"))
    )
    (comp (ref "C17")
      (value "100nF")
      (footprint "easyedapro:C0805")
      (description "Capacitance:100nF Tolerance:±10% Tolerance:±10% Voltage Rating:50V Temperature Coefficient:X7R")
      (fields
        (field (name "Manufacturer Part") "CC0805KRX7R9BB104")
        (field (name "Manufacturer") "YAGEO(国巨)")
      )
      (libsource (lib "easyedapro") (part "CC0805KRX7R9BB104"))
    )
    (comp (ref "C18")
      (value "10uF")
      (footprint "easyedapro:C0805")
      (description "Capacitance:10uF Tolerance:±10% Tolerance:±10% Voltage Rating:50V Temperature Coefficient:X5R")
      (fields
        (field (name "Manufacturer Part") "GRM21BR61H106KE43L")
        (field (name "Manufacturer") "muRata(村田)")
      )
      (libsource (lib "easyedapro") (part "GRM21BR61H106KE43L"))
    )
    (comp (ref "C19")
      (value "100nF")
      (footprint "easyedapro:C0805")
      (description "Capacitance:100nF Tolerance:±10% Tolerance:±10% Voltage Rating:50V Temperature Coefficient:X7R")
      (fields
        (field (name "Manufacturer Part") "CC0805KRX7R9BB104")
        (field (name "Manufacturer") "YAGEO(国巨)")
      )
      (libsource (lib "easyedapro") (part "CC0805KRX7R9BB104"))
    )
    (comp (ref "C20")
      (value "4.7uF")
      (footprint "easyedapro:C0805")
      (description "Capacitance:4.7uF Tolerance:±10% Tolerance:±10% Voltage Rating:25V Temperature Coefficient:X5R")
      (fields
        (field (name "Manufacturer Part") "CL21A475KAQNNNE")
        (field (name "Manufacturer") "SAMSUNG(三星)")
      )
      (libsource (lib "easyedapro") (part "CL21A475KAQNNNE"))
    )
    (comp (ref "C21")
      (value "1uF")
      (footprint "easyedapro:C0805")
      (description "Capacitance:1uF Tolerance:±20% Tolerance:±20% Voltage Rating:50V Temperature Coefficient:X7R")
      (fields
        (field (name "Manufacturer Part") "TCC0805X7R105M500FT")
        (field (name "Manufacturer") "CCTC(三环)")
      )
      (libsource (lib "easyedapro") (part "TCC0805X7R105M500FT"))
    )
    (comp (ref "C22")
      (value "10uF")
      (footprint "easyedapro:C0805")
      (description "Capacitance:10uF Tolerance:±10% Tolerance:±10% Voltage Rating:50V Temperature Coefficient:X5R")
      (fields
        (field (name "Manufacturer Part") "GRM21BR61H106KE43L")
        (field (name "Manufacturer") "muRata(村田)")
      )
      (libsource (lib "easyedapro") (part "GRM21BR61H106KE43L"))
    )
    (comp (ref "C86")
      (value "120p")
      (footprint "easyedapro:C0805")
      (description "Capacitance:100nF Tolerance:±10% Tolerance:±10% Voltage Rating:50V Temperature Coefficient:X7R")
      (fields
        (field (name "Manufacturer Part") "CC0805KRX7R9BB104")
        (field (name "Manufacturer") "YAGEO(国巨)")
      )
      (libsource (lib "easyedapro") (part "CC0805KRX7R9BB104"))
    )
    (comp (ref "C87")
      (value "120p")
      (footprint "easyedapro:C0805")
      (description "Capacitance:100nF Tolerance:±10% Tolerance:±10% Voltage Rating:50V Temperature Coefficient:X7R")
      (fields
        (field (name "Manufacturer Part") "CC0805KRX7R9BB104")
        (field (name "Manufacturer") "YAGEO(国巨)")
      )
      (libsource (lib "easyedapro") (part "CC0805KRX7R9BB104"))
    )
    (comp (ref "C88")
      (value "120p")
      (footprint "easyedapro:C0805")
      (description "Capacitance:100nF Tolerance:±10% Tolerance:±10% Voltage Rating:50V Temperature Coefficient:X7R")
      (fields
        (field (name "Manufacturer Part") "CC0805KRX7R9BB104")
        (field (name "Manufacturer") "YAGEO(国巨)")
      )
      (libsource (lib "easyedapro") (part "CC0805KRX7R9BB104"))
    )
    (comp (ref "C89")
      (value "120p")
      (footprint "easyedapro:C0805")
      (description "Capacitance:100nF Tolerance:±10% Tolerance:±10% Voltage Rating:50V Temperature Coefficient:X7R")
      (fields
        (field (name "Manufacturer Part") "CC0805KRX7R9BB104")
        (field (name "Manufacturer") "YAGEO(国巨)")
      )
      (libsource (lib "easyedapro") (part "CC0805KRX7R9BB104"))
    )
    (comp (ref "C90")
      (value "120p")
      (footprint "easyedapro:C0805")
      (description "Capacitance:100nF Tolerance:±10% Tolerance:±10% Voltage Rating:50V Temperature Coefficient:X7R")
      (fields
        (field (name "Manufacturer Part") "CC0805KRX7R9BB104")
        (field (name "Manufacturer") "YAGEO(国巨)")
      )
      (libsource (lib "easyedapro") (part "CC0805KRX7R9BB104"))
    )
    (comp (ref "C91")
      (value "120p")
      (footprint "easyedapro:C0805")
      (description "Capacitance:100nF Tolerance:±10% Tolerance:±10% Voltage Rating:50V Temperature Coefficient:X7R")
      (fields
        (field (name "Manufacturer Part") "CC0805KRX7R9BB104")
        (field (name "Manufacturer") "YAGEO(国巨)")
      )
      (libsource (lib "easyedapro") (part "CC0805KRX7R9BB104"))
    )
    (comp (ref "left_motor")
      (value "2.54-1*3P针")
      (footprint "easyedapro:HDR-TH_3P-P2.54-V-M-1")
      (fields (field (name "Manufacturer") "BOOMELE(博穆精密)"))
      (libsource (lib "easyedapro") (part "Header-Male-2.54_1x3"))
    )
    (comp (ref "right_motor")
      (value "2.54-1*3P针")
      (footprint "easyedapro:HDR-TH_3P-P2.54-V-M-1")
      (fields (field (name "Manufacturer") "BOOMELE(博穆精密)"))
      (libsource (lib "easyedapro") (part "Header-Male-2.54_1x3"))
    )
    (comp (ref "U10")
      (value "MP6541GQKT-Z")
      (footprint "easyedapro:QFN-26_L6.0-W6.0-P0.65-TL_MP6541")
      (fields (field (name "Manufacturer") "MPS(芯源)"))
      (libsource (lib "easyedapro") (part "MP6541GQKT-Z"))
    )
    (comp (ref "U11")
      (value "MP6541GQKT-Z")
      (footprint "easyedapro:QFN-26_L6.0-W6.0-P0.65-TL_MP6541")
      (fields (field (name "Manufacturer") "MPS(芯源)"))
      (libsource (lib "easyedapro") (part "MP6541GQKT-Z"))
    )
    (comp (ref "BAT")
      (value "PZ254V-11-02P")
      (footprint "easyedapro:HDR-TH_2P-P2.54-V-M")
      (fields (field (name "Manufacturer") "XFCN(兴飞)"))
      (libsource (lib "easyedapro") (part "PZ254V-11-02P"))
    )
    (comp (ref "C62")
      (value "100n")
      (footprint "easyedapro:C0805")
      (description "Capacitance:10uF Tolerance:±10% Tolerance:±10% Voltage Rating:25V Temperature Coefficient:X5R")
      (fields
        (field (name "Manufacturer Part") "CL21A106KAYNNNE")
        (field (name "Manufacturer") "SAMSUNG(三星)")
      )
      (libsource (lib "easyedapro") (part "CL21A106KAYNNNE"))
    )
    (comp (ref "C63")
      (value "100nF")
      (footprint "easyedapro:C0805")
      (description "Capacitance:100nF Tolerance:±10% Tolerance:±10% Voltage Rating:50V Temperature Coefficient:X7R")
      (fields
        (field (name "Manufacturer Part") "CC0805KRX7R9BB104")
        (field (name "Manufacturer") "YAGEO(国巨)")
      )
      (libsource (lib "easyedapro") (part "CC0805KRX7R9BB104"))
    )
    (comp (ref "C64")
      (value "10uF")
      (footprint "easyedapro:C0805")
      (description "Capacitance:10uF Tolerance:±10% Tolerance:±10% Voltage Rating:50V Temperature Coefficient:X5R")
      (fields
        (field (name "Manufacturer Part") "GRM21BR61H106KE43L")
        (field (name "Manufacturer") "muRata(村田)")
      )
      (libsource (lib "easyedapro") (part "GRM21BR61H106KE43L"))
    )
    (comp (ref "C65")
      (value "10uF")
      (footprint "easyedapro:C0805")
      (description "Capacitance:10uF Tolerance:±10% Tolerance:±10% Voltage Rating:50V Temperature Coefficient:X5R")
      (fields
        (field (name "Manufacturer Part") "GRM21BR61H106KE43L")
        (field (name "Manufacturer") "muRata(村田)")
      )
      (libsource (lib "easyedapro") (part "GRM21BR61H106KE43L"))
    )
    (comp (ref "C66")
      (value "100nF")
      (footprint "easyedapro:C0805")
      (description "Capacitance:100nF Tolerance:±10% Tolerance:±10% Voltage Rating:50V Temperature Coefficient:X7R")
      (fields
        (field (name "Manufacturer Part") "CC0805KRX7R9BB104")
        (field (name "Manufacturer") "YAGEO(国巨)")
      )
      (libsource (lib "easyedapro") (part "CC0805KRX7R9BB104"))
    )
    (comp (ref "C67")
      (value "10uF")
      (footprint "easyedapro:C0805")
      (description "Capacitance:10uF Tolerance:±10% Tolerance:±10% Voltage Rating:50V Temperature Coefficient:X5R")
      (fields
        (field (name "Manufacturer Part") "GRM21BR61H106KE43L")
        (field (name "Manufacturer") "muRata(村田)")
      )
      (libsource (lib "easyedapro") (part "GRM21BR61H106KE43L"))
    )
    (comp (ref "C74")
      (value "47uF")
      (footprint "easyedapro:CAP-SMD_L3.5-W2.8-R-RD")
      (fields (field (name "Manufacturer Part") "CA45-B010K476T") (field (name "Manufacturer") "湘怡中元/湘江"))
      (libsource (lib "easyedapro") (part "CA45-B010K476T"))
    )
    (comp (ref "C75")
      (value "47uF")
      (footprint "easyedapro:CAP-SMD_L3.5-W2.8-R-RD")
      (fields (field (name "Manufacturer Part") "CA45-B010K476T") (field (name "Manufacturer") "湘怡中元/湘江"))
      (libsource (lib "easyedapro") (part "CA45-B010K476T"))
    )
    (comp (ref "C84")
      (value "47uF")
      (footprint "easyedapro:CAP-SMD_L3.5-W2.8-R-RD")
      (fields (field (name "Manufacturer Part") "CA45-B010K476T") (field (name "Manufacturer") "湘怡中元/湘江"))
      (libsource (lib "easyedapro") (part "CA45-B010K476T"))
    )
    (comp (ref "C85")
      (value "47uF")
      (footprint "easyedapro:CAP-SMD_L3.5-W2.8-R-RD")
      (fields (field (name "Manufacturer Part") "CA45-B010K476T") (field (name "Manufacturer") "湘怡中元/湘江"))
      (libsource (lib "easyedapro") (part "CA45-B010K476T"))
    )
    (comp (ref "D1")
      (value "SS34")
      (footprint "easyedapro:SMA_L4.3-W2.6-LS5.2-RD")
      (fields (field (name "Manufacturer") "MDD(辰达半导体)"))
      (libsource (lib "easyedapro") (part "SS34_C8678"))
    )
    (comp (ref "L1")
      (value "4.7uH")
      (footprint "easyedapro:IND-SMD_L4.0-W4.0_FNR40XXS")
      (fields (field (name "Manufacturer Part") "FNR4030S4R7MT") (field (name "Manufacturer") "cjiang(长江微电)"))
      (libsource (lib "easyedapro") (part "FNR4030S4R7MT"))
    )
    (comp (ref "LED2")
      (value "YLED1206G")
      (footprint "easyedapro:LED1206-RD")
      (fields (field (name "Manufacturer") "YONGYUTAI(永裕泰)"))
      (libsource (lib "easyedapro") (part "YLED1206G"))
    )
    (comp (ref "R29")
      (value "330Ω")
      (footprint "easyedapro:R0805")
      (fields
        (field (name "Manufacturer Part") "0805W8F3300T5E")
        (field (name "Manufacturer") "UNI-ROYAL(厚声)")
      )
      (libsource (lib "easyedapro") (part "0805W8F3300T5E"))
    )
    (comp (ref "R30")
      (value "4.7kΩ")
      (footprint "easyedapro:R0805")
      (fields (field (name "Manufacturer Part") "FRC0805J472 TS") (field (name "Manufacturer") "FOJAN(富捷)"))
      (libsource (lib "easyedapro") (part "FRC0805J472 TS"))
    )
    (comp (ref "R31")
      (value "4.7kΩ")
      (footprint "easyedapro:R0805")
      (fields (field (name "Manufacturer Part") "FRC0805J472 TS") (field (name "Manufacturer") "FOJAN(富捷)"))
      (libsource (lib "easyedapro") (part "FRC0805J472 TS"))
    )
    (comp (ref "U12")
      (value "AP63203WU-7")
      (footprint "easyedapro:TSOT-26_L2.9-W1.6-P0.95-LS2.8-BL")
      (fields (field (name "Manufacturer") "DIODES(美台)"))
      (libsource (lib "easyedapro") (part "AP63203WU-7"))
    )
    (comp (ref "USB")
      (value "TYPE-C16PIN")
      (footprint "easyedapro:USB-C-SMD_TYPE-C16PIN")
      (fields (field (name "Manufacturer") "SHOU HAN(首韩)"))
      (libsource (lib "easyedapro") (part "TYPE-C16PIN"))
    )
  )
  (nets
    (net (code "1") (name "+3V3") (class "Default")
      (node (ref "BOOT") (pin "2") (pinfunction "2_2") (pintype "unspecified"))
      (node (ref "C1") (pin "2") (pinfunction "2_2") (pintype "unspecified"))
      (node (ref "C2") (pin "2") (pinfunction "2_2") (pintype "unspecified"))
      (node (ref "C3") (pin "2") (pinfunction "2_2") (pintype "unspecified"))
      (node (ref "C4") (pin "2") (pinfunction "2_2") (pintype "unspecified"))
      (node (ref "C5") (pin "2") (pinfunction "2_2") (pintype "unspecified"))
      (node (ref "C6") (pin "2") (pinfunction "2_2") (pintype "unspecified"))
      (node (ref "C63") (pin "2") (pinfunction "2_2") (pintype "unspecified"))
      (node (ref "C64") (pin "2") (pinfunction "2_2") (pintype "unspecified"))
      (node (ref "C65") (pin "2") (pinfunction "2_2") (pintype "unspecified"))
      (node (ref "C7") (pin "2") (pinfunction "2_2") (pintype "unspecified"))
      (node (ref "C72") (pin "2") (pinfunction "2_2") (pintype "unspecified"))
      (node (ref "C73") (pin "2") (pinfunction "2_2") (pintype "unspecified"))
      (node (ref "DEBUG") (pin "7") (pinfunction "7_7") (pintype "unspecified"))
      (node (ref "L1") (pin "2") (pinfunction "2_2") (pintype "unspecified"))
      (node (ref "LED1") (pin "1") (pinfunction "A_1") (pintype "unspecified"))
      (node (ref "R1") (pin "2") (pinfunction "2_2") (pintype "unspecified"))
      (node (ref "R10") (pin "2") (pinfunction "2_2") (pintype "unspecified"))
      (node (ref "R11") (pin "2") (pinfunction "2_2") (pintype "unspecified"))
      (node (ref "R12") (pin "2") (pinfunction "2_2") (pintype "unspecified"))
      (node (ref "R14") (pin "2") (pinfunction "2_2") (pintype "input"))
      (node (ref "R15") (pin "2") (pinfunction "2_2") (pintype "input"))
      (node (ref "R16") (pin "2") (pinfunction "2_2") (pintype "input"))
      (node (ref "R17") (pin "2") (pinfunction "2_2") (pintype "input"))
      (node (ref "R18") (pin "2") (pinfunction "2_2") (pintype "input"))
      (node (ref "R19") (pin "2") (pinfunction "2_2") (pintype "input"))
      (node (ref "R20") (pin "2") (pinfunction "2_2") (pintype "input"))
      (node (ref "R21") (pin "2") (pinfunction "2_2") (pintype "input"))
      (node (ref "R22") (pin "2") (pinfunction "2_2") (pintype "input"))
      (node (ref "R23") (pin "2") (pinfunction "2_2") (pintype "input"))
      (node (ref "R24") (pin "2") (pinfunction "2_2") (pintype "input"))
      (node (ref "R25") (pin "2") (pinfunction "2_2") (pintype "input"))
      (node (ref "R26") (pin "2") (pinfunction "2_2") (pintype "input"))
      (node (ref "R27") (pin "2") (pinfunction "2_2") (pintype "input"))
      (node (ref "R28") (pin "2") (pinfunction "2_2") (pintype "input"))
      (node (ref "R29") (pin "2") (pinfunction "2_2") (pintype "input"))
      (node (ref "R38") (pin "2") (pinfunction "2_2") (pintype "input"))
      (node (ref "R39") (pin "2") (pinfunction "2_2") (pintype "input"))
      (node (ref "R40") (pin "2") (pinfunction "2_2") (pintype "input"))
      (node (ref "R41") (pin "2") (pinfunction "2_2") (pintype "input"))
      (node (ref "R42") (pin "2") (pinfunction "2_2") (pintype "input"))
      (node (ref "R43") (pin "2") (pinfunction "2_2") (pintype "input"))
      (node (ref "R44") (pin "2") (pinfunction "2_2") (pintype "input"))
      (node (ref "R45") (pin "2") (pinfunction "2_2") (pintype "input"))
      (node (ref "R48") (pin "2") (pinfunction "2_2") (pintype "input"))
      (node (ref "R51") (pin "1") (pinfunction "1_1") (pintype "unspecified"))
      (node (ref "R52") (pin "1") (pinfunction "1_1") (pintype "unspecified"))
      (node (ref "R7") (pin "2") (pinfunction "2_2") (pintype "unspecified"))
      (node (ref "R8") (pin "2") (pinfunction "2_2") (pintype "unspecified"))
      (node (ref "R9") (pin "2") (pinfunction "2_2") (pintype "unspecified"))
      (node (ref "U1") (pin "13") (pinfunction "VDDA_13") (pintype "unspecified"))
      (node (ref "U1") (pin "19") (pinfunction "VDD_19") (pintype "unspecified"))
      (node (ref "U1") (pin "32") (pinfunction "VDD_32") (pintype "unspecified"))
      (node (ref "U1") (pin "48") (pinfunction "VDD_48") (pintype "unspecified"))
      (node (ref "U1") (pin "64") (pinfunction "VDD_64") (pintype "unspecified"))
      (node (ref "U10") (pin "2") (pinfunction "nSLEEP_2") (pintype "unspecified"))
      (node (ref "U11") (pin "2") (pinfunction "nSLEEP_2") (pintype "unspecified"))
      (node (ref "U12") (pin "1") (pinfunction "FB_1") (pintype "unspecified"))
      (node (ref "U14") (pin "4") (pinfunction "VCC_4") (pintype "unspecified"))
      (node (ref "U4") (pin "P$12") (pinfunction "CS_P$12") (pintype "bidirectional"))
      (node (ref "U4") (pin "P$5") (pinfunction "VDDIO_P$5") (pintype "bidirectional"))
      (node (ref "U4") (pin "P$8") (pinfunction "VDD_P$8") (pintype "bidirectional"))
      (node (ref "left_encoder") (pin "1") (pinfunction "1_1") (pintype "input"))
      (node (ref "right_encoder") (pin "1") (pinfunction "1_1") (pintype "input"))
    )
    (net (code "2") (name "ADC0") (class "Default")
      (node (ref "R38") (pin "1") (pinfunction "1_1") (pintype "input"))
      (node (ref "S1") (pin "2") (pinfunction "C_2") (pintype "input"))
      (node (ref "U1") (pin "14") (pinfunction "PA0-WKUP_14") (pintype "unspecified"))
    )
    (net (code "3") (name "ADC1") (class "Default")
      (node (ref "R39") (pin "1") (pinfunction "1_1") (pintype "input"))
      (node (ref "S2") (pin "2") (pinfunction "C_2") (pintype "input"))
      (node (ref "U1") (pin "15") (pinfunction "PA1_15") (pintype "unspecified"))
    )
    (net (code "4") (name "ADC2") (class "Default")
      (node (ref "R40") (pin "1") (pinfunction "1_1") (pintype "input"))
      (node (ref "S3") (pin "2") (pinfunction "C_2") (pintype "input"))
      (node (ref "U1") (pin "16") (pinfunction "PA2_16") (pintype "unspecified"))
    )
    (net (code "5") (name "ADC3") (class "Default")
      (node (ref "R41") (pin "1") (pinfunction "1_1") (pintype "input"))
      (node (ref "S4") (pin "2") (pinfunction "C_2") (pintype "input"))
      (node (ref "U1") (pin "17") (pinfunction "PA3_17") (pintype "unspecified"))
    )
    (net (code "6") (name "ADC4") (class "Default")
      (node (ref "R42") (pin "1") (pinfunction "1_1") (pintype "input"))
      (node (ref "S5") (pin "2") (pinfunction "C_2") (pintype "input"))
      (node (ref "U1") (pin "20") (pinfunction "PA4_20") (pintype "unspecified"))
    )
    (net (code "7") (name "ADC5") (class "Default")
      (node (ref "R43") (pin "1") (pinfunction "1_1") (pintype "input"))
      (node (ref "S6") (pin "2") (pinfunction "C_2") (pintype "input"))
      (node (ref "U1") (pin "21") (pinfunction "PA5_21") (pintype "unspecified"))
    )
    (net (code "8") (name "ADC6") (class "Default")
      (node (ref "R44") (pin "1") (pinfunction "1_1") (pintype "input"))
      (node (ref "S7") (pin "2") (pinfunction "C_2") (pintype "input"))
      (node (ref "U1") (pin "22") (pinfunction "PA6_22") (pintype "unspecified"))
    )
    (net (code "9") (name "ADC7") (class "Default")
      (node (ref "R45") (pin "1") (pinfunction "1_1") (pintype "input"))
      (node (ref "S8") (pin "2") (pinfunction "C_2") (pintype "input"))
      (node (ref "U1") (pin "23") (pinfunction "PA7_23") (pintype "unspecified"))
    )
    (net (code "10") (name "ADC8") (class "Default")
      (node (ref "R19") (pin "1") (pinfunction "1_1") (pintype "input"))
      (node (ref "S10") (pin "1") (pinfunction "C_1") (pintype "unspecified"))
      (node (ref "U1") (pin "25") (pinfunction "PB0_25") (pintype "unspecified"))
    )
    (net (code "11") (name "ADC9") (class "Default")
      (node (ref "R48") (pin "1") (pinfunction "1_1") (pintype "input"))
      (node (ref "S9") (pin "1") (pinfunction "C_1") (pintype "unspecified"))
      (node (ref "U1") (pin "26") (pinfunction "PB1_26") (pintype "unspecified"))
    )
    (net (code "12") (name "ADC10") (class "Default")
      (node (ref "R21") (pin "1") (pinfunction "1_1") (pintype "input"))
      (node (ref "S12") (pin "1") (pinfunction "C_1") (pintype "unspecified"))
      (node (ref "U1") (pin "8") (pinfunction "PC0_8") (pintype "unspecified"))
    )
    (net (code "13") (name "ADC11") (class "Default")
      (node (ref "R20") (pin "1") (pinfunction "1_1") (pintype "input"))
      (node (ref "S11") (pin "1") (pinfunction "C_1") (pintype "unspecified"))
      (node (ref "U1") (pin "9") (pinfunction "PC1_9") (pintype "unspecified"))
    )
    (net (code "14") (name "BOOT") (class "Default")
      (node (ref "BOOT") (pin "1") (pinfunction "1_1") (pintype "unspecified"))
      (node (ref "R2") (pin "1") (pinfunction "1_1") (pintype "unspecified"))
      (node (ref "U1") (pin "60") (pinfunction "BOOT0_60") (pintype "unspecified"))
    )
    (net (code "15") (name "ENC_L_SCL") (class "Default")
      (node (ref "R8") (pin "1") (pinfunction "1_1") (pintype "unspecified"))
      (node (ref "U1") (pin "34") (pinfunction "PB13_34") (pintype "unspecified"))
      (node (ref "left_encoder") (pin "3") (pinfunction "3_3") (pintype "input"))
    )
    (net (code "16") (name "ENC_L_SDA") (class "Default")
      (node (ref "R7") (pin "1") (pinfunction "1_1") (pintype "unspecified"))
      (node (ref "U1") (pin "33") (pinfunction "PB12_33") (pintype "unspecified"))
      (node (ref "left_encoder") (pin "2") (pinfunction "2_2") (pintype "input"))
    )
    (net (code "17") (name "ENC_R_SCL") (class "Default")
      (node (ref "R10") (pin "1") (pinfunction "1_1") (pintype "unspecified"))
      (node (ref "U1") (pin "52") (pinfunction "PC11_52") (pintype "unspecified"))
      (node (ref "right_encoder") (pin "3") (pinfunction "3_3") (pintype "input"))
    )
    (net (code "18") (name "ENC_R_SDA") (class "Default")
      (node (ref "R9") (pin "1") (pinfunction "1_1") (pintype "unspecified"))
      (node (ref "U1") (pin "51") (pinfunction "PC10_51") (pintype "unspecified"))
      (node (ref "right_encoder") (pin "2") (pinfunction "2_2") (pintype "input"))
    )
    (net (code "19") (name "GND") (class "Default")
      (node (ref "BAT") (pin "1") (pinfunction "1_1") (pintype "unspecified"))
      (node (ref "C1") (pin "1") (pinfunction "1_1") (pintype "unspecified"))
      (node (ref "C11") (pin "1") (pinfunction "1_1") (pintype "unspecified"))
      (node (ref "C12") (pin "1") (pinfunction "1_1") (pintype "unspecified"))
      (node (ref "C14") (pin "1") (pinfunction "1_1") (pintype "input"))
      (node (ref "C16") (pin "1") (pinfunction "1_1") (pintype "unspecified"))
      (node (ref "C17") (pin "1") (pinfunction "1_1") (pintype "unspecified"))
      (node (ref "C18") (pin "1") (pinfunction "1_1") (pintype "unspecified"))
      (node (ref "C2") (pin "1") (pinfunction "1_1") (pintype "unspecified"))
      (node (ref "C20") (pin "1") (pinfunction "1_1") (pintype "input"))
      (node (ref "C22") (pin "1") (pinfunction "1_1") (pintype "unspecified"))
      (node (ref "C3") (pin "1") (pinfunction "1_1") (pintype "unspecified"))
      (node (ref "C4") (pin "1") (pinfunction "1_1") (pintype "unspecified"))
      (node (ref "C5") (pin "1") (pinfunction "1_1") (pintype "unspecified"))
      (node (ref "C6") (pin "1") (pinfunction "1_1") (pintype "unspecified"))
      (node (ref "C63") (pin "1") (pinfunction "1_1") (pintype "unspecified"))
      (node (ref "C64") (pin "1") (pinfunction "1_1") (pintype "unspecified"))
      (node (ref "C65") (pin "1") (pinfunction "1_1") (pintype "unspecified"))
      (node (ref "C66") (pin "1") (pinfunction "1_1") (pintype "unspecified"))
      (node (ref "C67") (pin "1") (pinfunction "1_1") (pintype "unspecified"))
      (node (ref "C7") (pin "1") (pinfunction "1_1") (pintype "unspecified"))
      (node (ref "C72") (pin "1") (pinfunction "1_1") (pintype "unspecified"))
      (node (ref "C73") (pin "1") (pinfunction "1_1") (pintype "unspecified"))
      (node (ref "C74") (pin "2") (pinfunction "2_2") (pintype "input"))
      (node (ref "C75") (pin "2") (pinfunction "2_2") (pintype "input"))
      (node (ref "C8") (pin "2") (pinfunction "2_2") (pintype "unspecified"))
      (node (ref "C82") (pin "1") (pinfunction "1_1") (pintype "unspecified"))
      (node (ref "C83") (pin "1") (pinfunction "1_1") (pintype "unspecified"))
      (node (ref "C84") (pin "2") (pinfunction "2_2") (pintype "input"))
      (node (ref "C85") (pin "2") (pinfunction "2_2") (pintype "input"))
      (node (ref "C86") (pin "1") (pinfunction "1_1") (pintype "unspecified"))
      (node (ref "C87") (pin "1") (pinfunction "1_1") (pintype "unspecified"))
      (node (ref "C88") (pin "1") (pinfunction "1_1") (pintype "unspecified"))
      (node (ref "C89") (pin "1") (pinfunction "1_1") (pintype "unspecified"))
      (node (ref "C9") (pin "1") (pinfunction "1_1") (pintype "unspecified"))
      (node (ref "C90") (pin "1") (pinfunction "1_1") (pintype "unspecified"))
      (node (ref "C91") (pin "1") (pinfunction "1_1") (pintype "unspecified"))
      (node (ref "DEBUG") (pin "1") (pinfunction "1_1") (pintype "unspecified"))
      (node (ref "LED2") (pin "1") (pinfunction "K_1") (pintype "unspecified"))
      (node (ref "Q1") (pin "2") (pinfunction "S_2") (pintype "unspecified"))
      (node (ref "Q2") (pin "2") (pinfunction "S_2") (pintype "unspecified"))
      (node (ref "Q3") (pin "2") (pinfunction "S_2") (pintype "unspecified"))
      (node (ref "Q4") (pin "2") (pinfunction "S_2") (pintype "unspecified"))
      (node (ref "Q5") (pin "2") (pinfunction "S_2") (pintype "unspecified"))
      (node (ref "R13") (pin "1") (pinfunction "1_1") (pintype "input"))
      (node (ref "R2") (pin "2") (pinfunction "2_2") (pintype "unspecified"))
      (node (ref "R30") (pin "2") (pinfunction "2_2") (pintype "unspecified"))
      (node (ref "R31") (pin "2") (pinfunction "2_2") (pintype "unspecified"))
      (node (ref "R53") (pin "2") (pinfunction "2_2") (pintype "unspecified"))
      (node (ref "R55") (pin "2") (pinfunction "2_2") (pintype "unspecified"))
      (node (ref "R57") (pin "2") (pinfunction "2_2") (pintype "unspecified"))
      (node (ref "R59") (pin "2") (pinfunction "2_2") (pintype "unspecified"))
      (node (ref "RESET") (pin "3") (pinfunction "3_3") (pintype "unspecified"))
      (node (ref "S1") (pin "1") (pinfunction "E_1") (pintype "input"))
      (node (ref "S10") (pin "2") (pinfunction "A_2") (pintype "unspecified"))
      (node (ref "S11") (pin "2") (pinfunction "A_2") (pintype "unspecified"))
      (node (ref "S12") (pin "2") (pinfunction "A_2") (pintype "unspecified"))
      (node (ref "S2") (pin "1") (pinfunction "E_1") (pintype "input"))
      (node (ref "S3") (pin "1") (pinfunction "E_1") (pintype "input"))
      (node (ref "S4") (pin "1") (pinfunction "E_1") (pintype "input"))
      (node (ref "S5") (pin "1") (pinfunction "E_1") (pintype "input"))
      (node (ref "S6") (pin "1") (pinfunction "E_1") (pintype "input"))
      (node (ref "S7") (pin "1") (pinfunction "E_1") (pintype "input"))
      (node (ref "S8") (pin "1") (pinfunction "E_1") (pintype "input"))
      (node (ref "S9") (pin "2") (pinfunction "A_2") (pintype "unspecified"))
      (node (ref "U1") (pin "12") (pinfunction "VSSA_12") (pintype "unspecified"))
      (node (ref "U1") (pin "18") (pinfunction "VSS_18") (pintype "unspecified"))
      (node (ref "U1") (pin "31") (pinfunction "VSS_31") (pintype "unspecified"))
      (node (ref "U1") (pin "47") (pinfunction "VSS_47") (pintype "unspecified"))
      (node (ref "U1") (pin "63") (pinfunction "VSS_63") (pintype "unspecified"))
      (node (ref "U10") (pin "10") (pinfunction "LSS_10") (pintype "unspecified"))
      (node (ref "U10") (pin "12") (pinfunction "LSS_12") (pintype "unspecified"))
      (node (ref "U10") (pin "18") (pinfunction "GND_18") (pintype "unspecified"))
      (node (ref "U11") (pin "10") (pinfunction "LSS_10") (pintype "unspecified"))
      (node (ref "U11") (pin "12") (pinfunction "LSS_12") (pintype "unspecified"))
      (node (ref "U11") (pin "18") (pinfunction "GND_18") (pintype "unspecified"))
      (node (ref "U12") (pin "4") (pinfunction "GND_4") (pintype "unspecified"))
      (node (ref "U14") (pin "2") (pinfunction "VSS_2") (pintype "unspecified"))
      (node (ref "U14") (pin "5") (pinfunction "WP_5") (pintype "unspecified"))
      (node (ref "U4") (pin "P$1") (pinfunction "SDO/SA0_P$1") (pintype "bidirectional"))
      (node (ref "U4") (pin "P$2") (pinfunction "SDX_P$2") (pintype "bidirectional"))
      (node (ref "U4") (pin "P$3") (pinfunction "SCX_P$3") (pintype "bidirectional"))
      (node (ref "U4") (pin "P$6") (pinfunction "GND1_P$6") (pintype "bidirectional"))
      (node (ref "U4") (pin "P$7") (pinfunction "GND2_P$7") (pintype "bidirectional"))
      (node (ref "USB") (pin "1") (pinfunction "SHELL_1") (pintype "unspecified"))
      (node (ref "USB") (pin "2") (pinfunction "SHELL_2") (pintype "unspecified"))
      (node (ref "USB") (pin "3") (pinfunction "SHELL_3") (pintype "unspecified"))
      (node (ref "USB") (pin "4") (pinfunction "SHELL_4") (pintype "unspecified"))
      (node (ref "USB") (pin "A1B12") (pinfunction "GND_A1B12") (pintype "unspecified"))
      (node (ref "USB") (pin "B1A12") (pinfunction "GND_B1A12") (pintype "unspecified"))
      (node (ref "USER") (pin "3") (pinfunction "3_3") (pintype "unspecified"))
      (node (ref "left_encoder") (pin "4") (pinfunction "4_4") (pintype "input"))
      (node (ref "right_encoder") (pin "4") (pinfunction "4_4") (pintype "input"))
    )
    (net (code "20") (name "IR_FL") (class "Default")
      (node (ref "Q2") (pin "1") (pinfunction "G_1") (pintype "unspecified"))
      (node (ref "R53") (pin "1") (pinfunction "1_1") (pintype "unspecified"))
      (node (ref "U1") (pin "41") (pinfunction "PA8_41") (pintype "unspecified"))
    )
    (net (code "21") (name "IR_FR") (class "Default")
      (node (ref "Q5") (pin "1") (pinfunction "G_1") (pintype "unspecified"))
      (node (ref "R59") (pin "1") (pinfunction "1_1") (pintype "unspecified"))
      (node (ref "U1") (pin "11") (pinfunction "PC3_11") (pintype "unspecified"))
    )
    (net (code "22") (name "IR_L") (class "Default")
      (node (ref "Q3") (pin "1") (pinfunction "G_1") (pintype "unspecified"))
      (node (ref "R55") (pin "1") (pinfunction "1_1") (pintype "unspecified"))
      (node (ref "U1") (pin "53") (pinfunction "PC12_53") (pintype "unspecified"))
    )
    (net (code "23") (name "IR_R") (class "Default")
      (node (ref "Q4") (pin "1") (pinfunction "G_1") (pintype "unspecified"))
      (node (ref "R57") (pin "1") (pinfunction "1_1") (pintype "unspecified"))
      (node (ref "U1") (pin "54") (pinfunction "PD2_54") (pintype "unspecified"))
    )
    (net (code "24") (name "KEY0") (class "Default")
      (node (ref "U1") (pin "24") (pinfunction "PC4_24") (pintype "unspecified"))
      (node (ref "USER") (pin "2") (pinfunction "2_2") (pintype "unspecified"))
    )
    (net (code "25") (name "LE") (class "Default")
      (node (ref "U1") (pin "40") (pinfunction "PC9_40") (pintype "unspecified"))
      (node (ref "U10") (pin "3") (pinfunction "ENA_3") (pintype "unspecified"))
      (node (ref "U10") (pin "4") (pinfunction "ENB_4") (pintype "unspecified"))
      (node (ref "U10") (pin "5") (pinfunction "ENC_5") (pintype "unspecified"))
    )
    (net (code "26") (name "LED0") (class "Default")
      (node (ref "R4") (pin "2") (pinfunction "2_2") (pintype "unspecified"))
      (node (ref "U1") (pin "27") (pinfunction "PB2_27") (pintype "unspecified"))
    )
    (net (code "27") (name "LED1") (class "Default")
      (node (ref "R5") (pin "2") (pinfunction "2_2") (pintype "unspecified"))
      (node (ref "U1") (pin "28") (pinfunction "PB10_28") (pintype "unspecified"))
    )
    (net (code "28") (name "LED2") (class "Default")
      (node (ref "R6") (pin "2") (pinfunction "2_2") (pintype "unspecified"))
      (node (ref "U1") (pin "29") (pinfunction "PB11_29") (pintype "unspecified"))
    )
    (net (code "29") (name "LED_CONTROL") (class "Default")
      (node (ref "Q1") (pin "1") (pinfunction "G_1") (pintype "unspecified"))
      (node (ref "R13") (pin "2") (pinfunction "2_2") (pintype "input"))
      (node (ref "U1") (pin "10") (pinfunction "PC2_10") (pintype "unspecified"))
    )
    (net (code "30") (name "MLA") (class "Default")
      (node (ref "C86") (pin "2") (pinfunction "2_2") (pintype "unspecified"))
      (node (ref "U10") (pin "26") (pinfunction "SA_26") (pintype "unspecified"))
      (node (ref "U10") (pin "9") (pinfunction "SA_9") (pintype "unspecified"))
      (node (ref "left_motor") (pin "1") (pinfunction "1_1") (pintype "input"))
    )
    (net (code "31") (name "MLB") (class "Default")
      (node (ref "C87") (pin "2") (pinfunction "2_2") (pintype "unspecified"))
      (node (ref "U10") (pin "11") (pinfunction "SB_11") (pintype "unspecified"))
      (node (ref "U10") (pin "24") (pinfunction "SB_24") (pintype "unspecified"))
      (node (ref "left_motor") (pin "2") (pinfunction "2_2") (pintype "input"))
    )
    (net (code "32") (name "MLC") (class "Default")
      (node (ref "C88") (pin "2") (pinfunction "2_2") (pintype "unspecified"))
      (node (ref "U10") (pin "13") (pinfunction "SC_13") (pintype "unspecified"))
      (node (ref "U10") (pin "22") (pinfunction "SC_22") (pintype "unspecified"))
      (node (ref "left_motor") (pin "3") (pinfunction "3_3") (pintype "input"))
    )
    (net (code "33") (name "MRA") (class "Default")
      (node (ref "C89") (pin "2") (pinfunction "2_2") (pintype "unspecified"))
      (node (ref "U11") (pin "26") (pinfunction "SA_26") (pintype "unspecified"))
      (node (ref "U11") (pin "9") (pinfunction "SA_9") (pintype "unspecified"))
      (node (ref "right_motor") (pin "1") (pinfunction "1_1") (pintype "input"))
    )
    (net (code "34") (name "MRB") (class "Default")
      (node (ref "C90") (pin "2") (pinfunction "2_2") (pintype "unspecified"))
      (node (ref "U11") (pin "11") (pinfunction "SB_11") (pintype "unspecified"))
      (node (ref "U11") (pin "24") (pinfunction "SB_24") (pintype "unspecified"))
      (node (ref "right_motor") (pin "2") (pinfunction "2_2") (pintype "input"))
    )
    (net (code "35") (name "MRC") (class "Default")
      (node (ref "C91") (pin "2") (pinfunction "2_2") (pintype "unspecified"))
      (node (ref "U11") (pin "13") (pinfunction "SC_13") (pintype "unspecified"))
      (node (ref "U11") (pin "22") (pinfunction "SC_22") (pintype "unspecified"))
      (node (ref "right_motor") (pin "3") (pinfunction "3_3") (pintype "input"))
    )
    (net (code "36") (name "Net-(LED1-C-Pad2)") (class "Default")
      (node (ref "LED1") (pin "2") (pinfunction "C_2") (pintype "unspecified"))
      (node (ref "R4") (pin "1") (pinfunction "1_1") (pintype "unspecified"))
    )
    (net (code "37") (name "Net-(LED1-C-Pad3)") (class "Default")
      (node (ref "LED1") (pin "3") (pinfunction "C_3") (pintype "unspecified"))
      (node (ref "R5") (pin "1") (pinfunction "1_1") (pintype "unspecified"))
    )
    (net (code "38") (name "Net-(LED1-C-Pad4)") (class "Default")
      (node (ref "LED1") (pin "4") (pinfunction "C_4") (pintype "unspecified"))
      (node (ref "R6") (pin "1") (pinfunction "1_1") (pintype "unspecified"))
    )
    (net (code "39") (name "Net-(LED2-A)") (class "Default")
      (node (ref "LED2") (pin "2") (pinfunction "A_2") (pintype "unspecified"))
      (node (ref "R29") (pin "1") (pinfunction "1_1") (pintype "input"))
    )
    (net (code "40") (name "Net-(LED3-A)") (class "Default")
      (node (ref "LED3") (pin "1") (pinfunction "A_1") (pintype "unspecified"))
      (node (ref "R14") (pin "1") (pinfunction "1_1") (pintype "input"))
    )
    (net (code "41") (name "Net-(LED4-A)") (class "Default")
      (node (ref "LED4") (pin "1") (pinfunction "A_1") (pintype "unspecified"))
      (node (ref "R15") (pin "1") (pinfunction "1_1") (pintype "input"))
    )
    (net (code "42") (name "Net-(LED5-A)") (class "Default")
      (node (ref "LED5") (pin "1") (pinfunction "A_1") (pintype "unspecified"))
      (node (ref "R16") (pin "1") (pinfunction "1_1") (pintype "input"))
    )
    (net (code "43") (name "Net-(LED6-A)") (class "Default")
      (node (ref "LED6") (pin "1") (pinfunction "A_1") (pintype "unspecified"))
      (node (ref "R17") (pin "1") (pinfunction "1_1") (pintype "input"))
    )
    (net (code "44") (name "Net-(LED7-A)") (class "Default")
      (node (ref "LED7") (pin "1") (pinfunction "A_1") (pintype "unspecified"))
      (node (ref "R18") (pin "1") (pinfunction "1_1") (pintype "input"))
    )
    (net (code "45") (name "Net-(LED8-A)") (class "Default")
      (node (ref "LED8") (pin "1") (pinfunction "A_1") (pintype "unspecified"))
      (node (ref "R26") (pin "1") (pinfunction "1_1") (pintype "input"))
    )
    (net (code "46") (name "Net-(LED9-A)") (class "Default")
      (node (ref "LED9") (pin "1") (pinfunction "A_1") (pintype "unspecified"))
      (node (ref "R27") (pin "1") (pinfunction "1_1") (pintype "input"))
    )
    (net (code "47") (name "Net-(LED10-A)") (class "Default")
      (node (ref "LED10") (pin "1") (pinfunction "A_1") (pintype "unspecified"))
      (node (ref "R28") (pin "1") (pinfunction "1_1") (pintype "input"))
    )
    (net (code "48") (name "Net-(LED10-K)") (class "Default")
      (node (ref "LED10") (pin "2") (pinfunction "K_2") (pintype "unspecified"))
      (node (ref "LED3") (pin "2") (pinfunction "K_2") (pintype "unspecified"))
      (node (ref "LED4") (pin "2") (pinfunction "K_2") (pintype "unspecified"))
      (node (ref "LED5") (pin "2") (pinfunction "K_2") (pintype "unspecified"))
      (node (ref "LED6") (pin "2") (pinfunction "K_2") (pintype "unspecified"))
      (node (ref "LED7") (pin "2") (pinfunction "K_2") (pintype "unspecified"))
      (node (ref "LED8") (pin "2") (pinfunction "K_2") (pintype "unspecified"))
      (node (ref "LED9") (pin "2") (pinfunction "K_2") (pintype "unspecified"))
      (node (ref "Q1") (pin "3") (pinfunction "D_3") (pintype "unspecified"))
    )
    (net (code "49") (name "Net-(LED11-A)") (class "Default")
      (node (ref "LED11") (pin "1") (pinfunction "A_1") (pintype "unspecified"))
      (node (ref "R22") (pin "1") (pinfunction "1_1") (pintype "input"))
    )
    (net (code "50") (name "Net-(LED11-C)") (class "Default")
      (node (ref "LED11") (pin "2") (pinfunction "C_2") (pintype "unspecified"))
      (node (ref "Q2") (pin "3") (pinfunction "D_3") (pintype "unspecified"))
    )
    (net (code "51") (name "Net-(LED12-A)") (class "Default")
      (node (ref "LED12") (pin "1") (pinfunction "A_1") (pintype "unspecified"))
      (node (ref "R23") (pin "1") (pinfunction "1_1") (pintype "input"))
    )
    (net (code "52") (name "Net-(LED12-C)") (class "Default")
      (node (ref "LED12") (pin "2") (pinfunction "C_2") (pintype "unspecified"))
      (node (ref "Q3") (pin "3") (pinfunction "D_3") (pintype "unspecified"))
    )
    (net (code "53") (name "Net-(LED13-A)") (class "Default")
      (node (ref "LED13") (pin "1") (pinfunction "A_1") (pintype "unspecified"))
      (node (ref "R24") (pin "1") (pinfunction "1_1") (pintype "input"))
    )
    (net (code "54") (name "Net-(LED13-C)") (class "Default")
      (node (ref "LED13") (pin "2") (pinfunction "C_2") (pintype "unspecified"))
      (node (ref "Q4") (pin "3") (pinfunction "D_3") (pintype "unspecified"))
    )
    (net (code "55") (name "Net-(LED14-A)") (class "Default")
      (node (ref "LED14") (pin "1") (pinfunction "A_1") (pintype "unspecified"))
      (node (ref "R25") (pin "1") (pinfunction "1_1") (pintype "input"))
    )
    (net (code "56") (name "Net-(LED14-C)") (class "Default")
      (node (ref "LED14") (pin "2") (pinfunction "C_2") (pintype "unspecified"))
      (node (ref "Q5") (pin "3") (pinfunction "D_3") (pintype "unspecified"))
    )
    (net (code "57") (name "Net-(U1-PH0-OSC_IN)") (class "Default")
      (node (ref "C82") (pin "2") (pinfunction "2_2") (pintype "unspecified"))
      (node (ref "U1") (pin "5") (pinfunction "PH0-OSC_IN_5") (pintype "unspecified"))
      (node (ref "X1") (pin "3") (pinfunction "OSC2_3") (pintype "unspecified"))
    )
    (net (code "58") (name "Net-(U1-PH1-OSC_OUT)") (class "Default")
      (node (ref "C83") (pin "2") (pinfunction "2_2") (pintype "unspecified"))
      (node (ref "U1") (pin "6") (pinfunction "PH1-OSC_OUT_6") (pintype "unspecified"))
      (node (ref "X1") (pin "1") (pinfunction "OSC1_1") (pintype "unspecified"))
    )
    (net (code "59") (name "Net-(U1-VCAP_1)") (class "Default")
      (node (ref "C8") (pin "1") (pinfunction "1_1") (pintype "unspecified"))
      (node (ref "U1") (pin "30") (pinfunction "VCAP_1_30") (pintype "unspecified"))
    )
    (net (code "60") (name "Net-(U10-CP1)") (class "Default")
      (node (ref "C13") (pin "2") (pinfunction "2_2") (pintype "unspecified"))
      (node (ref "U10") (pin "20") (pinfunction "CP1_20") (pintype "unspecified"))
    )
    (net (code "61") (name "Net-(U10-CP2)") (class "Default")
      (node (ref "C13") (pin "1") (pinfunction "1_1") (pintype "unspecified"))
      (node (ref "U10") (pin "21") (pinfunction "CP2_21") (pintype "unspecified"))
    )
    (net (code "62") (name "Net-(U10-VCP)") (class "Default")
      (node (ref "C15") (pin "2") (pinfunction "2_2") (pintype "unspecified"))
      (node (ref "U10") (pin "19") (pinfunction "VCP_19") (pintype "unspecified"))
    )
    (net (code "63") (name "Net-(U10-VG)") (class "Default")
      (node (ref "C14") (pin "2") (pinfunction "2_2") (pintype "input"))
      (node (ref "U10") (pin "14") (pinfunction "VG_14") (pintype "unspecified"))
    )
    (net (code "64") (name "Net-(U11-CP1)") (class "Default")
      (node (ref "C19") (pin "2") (pinfunction "2_2") (pintype "unspecified"))
      (node (ref "U11") (pin "20") (pinfunction "CP1_20") (pintype "unspecified"))
    )
    (net (code "65") (name "Net-(U11-CP2)") (class "Default")
      (node (ref "C19") (pin "1") (pinfunction "1_1") (pintype "unspecified"))
      (node (ref "U11") (pin "21") (pinfunction "CP2_21") (pintype "unspecified"))
    )
    (net (code "66") (name "Net-(U11-VCP)") (class "Default")
      (node (ref "C21") (pin "2") (pinfunction "2_2") (pintype "unspecified"))
      (node (ref "U11") (pin "19") (pinfunction "VCP_19") (pintype "unspecified"))
    )
    (net (code "67") (name "Net-(U11-VG)") (class "Default")
      (node (ref "C20") (pin "2") (pinfunction "2_2") (pintype "input"))
      (node (ref "U11") (pin "14") (pinfunction "VG_14") (pintype "unspecified"))
    )
    (net (code "68") (name "Net-(U12-BST)") (class "Default")
      (node (ref "C62") (pin "2") (pinfunction "2_2") (pintype "unspecified"))
      (node (ref "U12") (pin "6") (pinfunction "BST_6") (pintype "unspecified"))
    )
    (net (code "69") (name "Net-(U12-SW)") (class "Default")
      (node (ref "C62") (pin "1") (pinfunction "1_1") (pintype "unspecified"))
      (node (ref "L1") (pin "1") (pinfunction "1_1") (pintype "unspecified"))
      (node (ref "U12") (pin "5") (pinfunction "SW_5") (pintype "unspecified"))
    )
    (net (code "70") (name "Net-(USB-CC1)") (class "Default")
      (node (ref "R31") (pin "1") (pinfunction "1_1") (pintype "unspecified"))
      (node (ref "USB") (pin "A5") (pinfunction "CC1_A5") (pintype "unspecified"))
    )
    (net (code "71") (name "Net-(USB-CC2)") (class "Default")
      (node (ref "R30") (pin "1") (pinfunction "1_1") (pintype "unspecified"))
      (node (ref "USB") (pin "B5") (pinfunction "CC2_B5") (pintype "unspecified"))
    )
    (net (code "72") (name "PLA") (class "Default")
      (node (ref "U1") (pin "37") (pinfunction "PC6_37") (pintype "unspecified"))
      (node (ref "U10") (pin "6") (pinfunction "PWMA_6") (pintype "unspecified"))
    )
    (net (code "73") (name "PLB") (class "Default")
      (node (ref "U1") (pin "38") (pinfunction "PC7_38") (pintype "unspecified"))
      (node (ref "U10") (pin "7") (pinfunction "PWMB_7") (pintype "unspecified"))
    )
    (net (code "74") (name "PLC") (class "Default")
      (node (ref "U1") (pin "39") (pinfunction "PC8_39") (pintype "unspecified"))
      (node (ref "U10") (pin "8") (pinfunction "PWMC_8") (pintype "unspecified"))
    )
    (net (code "75") (name "PRA") (class "Default")
      (node (ref "U1") (pin "58") (pinfunction "PB6_58") (pintype "unspecified"))
      (node (ref "U11") (pin "6") (pinfunction "PWMA_6") (pintype "unspecified"))
    )
    (net (code "76") (name "PRB") (class "Default")
      (node (ref "U1") (pin "59") (pinfunction "PB7_59") (pintype "unspecified"))
      (node (ref "U11") (pin "7") (pinfunction "PWMB_7") (pintype "unspecified"))
    )
    (net (code "77") (name "PRC") (class "Default")
      (node (ref "U1") (pin "61") (pinfunction "PB8_61") (pintype "unspecified"))
      (node (ref "U11") (pin "8") (pinfunction "PWMC_8") (pintype "unspecified"))
    )
    (net (code "78") (name "RE") (class "Default")
      (node (ref "U1") (pin "62") (pinfunction "PB9_62") (pintype "unspecified"))
      (node (ref "U11") (pin "3") (pinfunction "ENA_3") (pintype "unspecified"))
      (node (ref "U11") (pin "4") (pinfunction "ENB_4") (pintype "unspecified"))
      (node (ref "U11") (pin "5") (pinfunction "ENC_5") (pintype "unspecified"))
    )
    (net (code "79") (name "RESET") (class "Default")
      (node (ref "C9") (pin "2") (pinfunction "2_2") (pintype "unspecified"))
      (node (ref "DEBUG") (pin "4") (pinfunction "4_4") (pintype "unspecified"))
      (node (ref "R1") (pin "1") (pinfunction "1_1") (pintype "unspecified"))
      (node (ref "RESET") (pin "2") (pinfunction "2_2") (pintype "unspecified"))
      (node (ref "U1") (pin "7") (pinfunction "NRST_7") (pintype "unspecified"))
    )
    (net (code "80") (name "SCL") (class "Default")
      (node (ref "R12") (pin "1") (pinfunction "1_1") (pintype "unspecified"))
      (node (ref "U1") (pin "35") (pinfunction "PB14_35") (pintype "unspecified"))
      (node (ref "U4") (pin "P$13") (pinfunction "SCL_P$13") (pintype "bidirectional"))
    )
    (net (code "81") (name "SCL_E") (class "Default")
      (node (ref "R51") (pin "2") (pinfunction "2_2") (pintype "unspecified"))
      (node (ref "U1") (pin "56") (pinfunction "PB4_56") (pintype "unspecified"))
      (node (ref "U14") (pin "1") (pinfunction "SCL_1") (pintype "unspecified"))
    )
    (net (code "82") (name "SDA") (class "Default")
      (node (ref "R11") (pin "1") (pinfunction "1_1") (pintype "unspecified"))
      (node (ref "U1") (pin "36") (pinfunction "PB15_36") (pintype "unspecified"))
      (node (ref "U4") (pin "P$14") (pinfunction "SDA_P$14") (pintype "bidirectional"))
    )
    (net (code "83") (name "SDA_E") (class "Default")
      (node (ref "R52") (pin "2") (pinfunction "2_2") (pintype "unspecified"))
      (node (ref "U1") (pin "57") (pinfunction "PB5_57") (pintype "unspecified"))
      (node (ref "U14") (pin "3") (pinfunction "SDA_3") (pintype "unspecified"))
    )
    (net (code "84") (name "SWCLK") (class "Default")
      (node (ref "DEBUG") (pin "8") (pinfunction "8_8") (pintype "unspecified"))
      (node (ref "U1") (pin "49") (pinfunction "PA14_49") (pintype "unspecified"))
    )
    (net (code "85") (name "SWDIO") (class "Default")
      (node (ref "DEBUG") (pin "6") (pinfunction "6_6") (pintype "unspecified"))
      (node (ref "U1") (pin "46") (pinfunction "PA13_46") (pintype "unspecified"))
    )
    (net (code "86") (name "SWO") (class "Default")
      (node (ref "DEBUG") (pin "2") (pinfunction "2_2") (pintype "unspecified"))
      (node (ref "U1") (pin "55") (pinfunction "PB3_55") (pintype "unspecified"))
    )
    (net (code "87") (name "UART_RX") (class "Default")
      (node (ref "DEBUG") (pin "3") (pinfunction "3_3") (pintype "unspecified"))
      (node (ref "U1") (pin "43") (pinfunction "PA10_43") (pintype "unspecified"))
    )
    (net (code "88") (name "UART_TX") (class "Default")
      (node (ref "DEBUG") (pin "5") (pinfunction "5_5") (pintype "unspecified"))
      (node (ref "U1") (pin "42") (pinfunction "PA9_42") (pintype "unspecified"))
    )
    (net (code "89") (name "USB_DN") (class "Default")
      (node (ref "U1") (pin "44") (pinfunction "PA11_44") (pintype "unspecified"))
      (node (ref "USB") (pin "A7") (pinfunction "DN1_A7") (pintype "unspecified"))
      (node (ref "USB") (pin "B7") (pinfunction "DN2_B7") (pintype "unspecified"))
    )
    (net (code "90") (name "USB_DP") (class "Default")
      (node (ref "U1") (pin "45") (pinfunction "PA12_45") (pintype "unspecified"))
      (node (ref "USB") (pin "A6") (pinfunction "DP1_A6") (pintype "unspecified"))
      (node (ref "USB") (pin "B6") (pinfunction "DP2_B6") (pintype "unspecified"))
    )
    (net (code "91") (name "VBAT") (class "Default")
      (node (ref "BAT") (pin "2") (pinfunction "2_2") (pintype "unspecified"))
      (node (ref "C11") (pin "2") (pinfunction "2_2") (pintype "unspecified"))
      (node (ref "C12") (pin "2") (pinfunction "2_2") (pintype "unspecified"))
      (node (ref "C15") (pin "1") (pinfunction "1_1") (pintype "unspecified"))
      (node (ref "C16") (pin "2") (pinfunction "2_2") (pintype "unspecified"))
      (node (ref "C17") (pin "2") (pinfunction "2_2") (pintype "unspecified"))
      (node (ref "C18") (pin "2") (pinfunction "2_2") (pintype "unspecified"))
      (node (ref "C21") (pin "1") (pinfunction "1_1") (pintype "unspecified"))
      (node (ref "C22") (pin "2") (pinfunction "2_2") (pintype "unspecified"))
      (node (ref "C66") (pin "2") (pinfunction "2_2") (pintype "unspecified"))
      (node (ref "C67") (pin "2") (pinfunction "2_2") (pintype "unspecified"))
      (node (ref "C74") (pin "1") (pinfunction "1_1") (pintype "input"))
      (node (ref "C75") (pin "1") (pinfunction "1_1") (pintype "input"))
      (node (ref "C84") (pin "1") (pinfunction "1_1") (pintype "input"))
      (node (ref "C85") (pin "1") (pinfunction "1_1") (pintype "input"))
      (node (ref "D1") (pin "1") (pinfunction "K_1") (pintype "unspecified"))
      (node (ref "U10") (pin "23") (pinfunction "VIN_23") (pintype "unspecified"))
      (node (ref "U10") (pin "25") (pinfunction "VIN_25") (pintype "unspecified"))
      (node (ref "U11") (pin "23") (pinfunction "VIN_23") (pintype "unspecified"))
      (node (ref "U11") (pin "25") (pinfunction "VIN_25") (pintype "unspecified"))
      (node (ref "U12") (pin "2") (pinfunction "EN_2") (pintype "unspecified"))
      (node (ref "U12") (pin "3") (pinfunction "VIN_3") (pintype "unspecified"))
    )
    (net (code "92") (name "VBUS") (class "Default")
      (node (ref "D1") (pin "2") (pinfunction "A_2") (pintype "unspecified"))
      (node (ref "USB") (pin "A4B9") (pinfunction "VBUS_A4B9") (pintype "unspecified"))
      (node (ref "USB") (pin "B4A9") (pinfunction "VBUS_B4A9") (pintype "unspecified"))
    )
    (net (code "93") (name "unconnected-(RESET-Pad1)") (class "Default")
      (node (ref "RESET") (pin "1") (pinfunction "1_1") (pintype "unspecified"))
    )
    (net (code "94") (name "unconnected-(RESET-Pad4)") (class "Default")
      (node (ref "RESET") (pin "4") (pinfunction "4_4") (pintype "unspecified"))
    )
    (net (code "95") (name "unconnected-(U1-PA15-Pad50)") (class "Default")
      (node (ref "U1") (pin "50") (pinfunction "PA15_50") (pintype "unspecified"))
    )
    (net (code "96") (name "unconnected-(U1-PC13-Pad2)") (class "Default")
      (node (ref "U1") (pin "2") (pinfunction "PC13_2") (pintype "unspecified"))
    )
    (net (code "97") (name "unconnected-(U1-PC14-OSC32_IN-Pad3)") (class "Default")
      (node (ref "U1") (pin "3") (pinfunction "PC14-OSC32_IN_3") (pintype "unspecified"))
    )
    (net (code "98") (name "unconnected-(U1-PC15-OSC32_OUT-Pad4)") (class "Default")
      (node (ref "U1") (pin "4") (pinfunction "PC15-OSC32_OUT_4") (pintype "unspecified"))
    )
    (net (code "99") (name "unconnected-(U1-VBAT-Pad1)") (class "Default")
      (node (ref "U1") (pin "1") (pinfunction "VBAT_1") (pintype "unspecified"))
    )
    (net (code "100") (name "unconnected-(U4-INT1-PadP$4)") (class "Default")
      (node (ref "U4") (pin "P$4") (pinfunction "INT1_P$4") (pintype "bidirectional"))
    )
    (net (code "101") (name "unconnected-(U4-INT2-PadP$9)") (class "Default")
      (node (ref "U4") (pin "P$9") (pinfunction "INT2_P$9") (pintype "bidirectional"))
    )
    (net (code "102") (name "unconnected-(U4-NC1-PadP$10)") (class "Default")
      (node (ref "U4") (pin "P$10") (pinfunction "NC1_P$10") (pintype "bidirectional"))
    )
    (net (code "103") (name "unconnected-(U4-NC2-PadP$11)") (class "Default")
      (node (ref "U4") (pin "P$11") (pinfunction "NC2_P$11") (pintype "bidirectional"))
    )
    (net (code "104") (name "unconnected-(U10-SOA-Pad15)") (class "Default")
      (node (ref "U10") (pin "15") (pinfunction "SOA_15") (pintype "unspecified"))
    )
    (net (code "105") (name "unconnected-(U10-SOB-Pad16)") (class "Default")
      (node (ref "U10") (pin "16") (pinfunction "SOB_16") (pintype "unspecified"))
    )
    (net (code "106") (name "unconnected-(U10-SOC-Pad17)") (class "Default")
      (node (ref "U10") (pin "17") (pinfunction "SOC_17") (pintype "unspecified"))
    )
    (net (code "107") (name "unconnected-(U10-nFAULT-Pad1)") (class "Default")
      (node (ref "U10") (pin "1") (pinfunction "nFAULT_1") (pintype "unspecified"))
    )
    (net (code "108") (name "unconnected-(U11-SOA-Pad15)") (class "Default")
      (node (ref "U11") (pin "15") (pinfunction "SOA_15") (pintype "unspecified"))
    )
    (net (code "109") (name "unconnected-(U11-SOB-Pad16)") (class "Default")
      (node (ref "U11") (pin "16") (pinfunction "SOB_16") (pintype "unspecified"))
    )
    (net (code "110") (name "unconnected-(U11-SOC-Pad17)") (class "Default")
      (node (ref "U11") (pin "17") (pinfunction "SOC_17") (pintype "unspecified"))
    )
    (net (code "111") (name "unconnected-(U11-nFAULT-Pad1)") (class "Default")
      (node (ref "U11") (pin "1") (pinfunction "nFAULT_1") (pintype "unspecified"))
    )
    (net (code "112") (name "unconnected-(USB-SBU1-PadA8)") (class "Default")
      (node (ref "USB") (pin "A8") (pinfunction "SBU1_A8") (pintype "unspecified"))
    )
    (net (code "113") (name "unconnected-(USB-SBU2-PadB8)") (class "Default")
      (node (ref "USB") (pin "B8") (pinfunction "SBU2_B8") (pintype "unspecified"))
    )
    (net (code "114") (name "unconnected-(USER-Pad1)") (class "Default")
      (node (ref "USER") (pin "1") (pinfunction "1_1") (pintype "unspecified"))
    )
    (net (code "115") (name "unconnected-(USER-Pad4)") (class "Default")
      (node (ref "USER") (pin "4") (pinfunction "4_4") (pintype "unspecified"))
    )
    (net (code "116") (name "unconnected-(X1-GND-Pad2)") (class "Default")
      (node (ref "X1") (pin "2") (pinfunction "GND_2") (pintype "unspecified"))
    )
    (net (code "117") (name "unconnected-(X1-GND-Pad4)") (class "Default")
      (node (ref "X1") (pin "4") (pinfunction "GND_4") (pintype "unspecified"))
    )
  )
)
